# Sheet1.net
KiCad netlist of a schematic drawn in Altium Designer
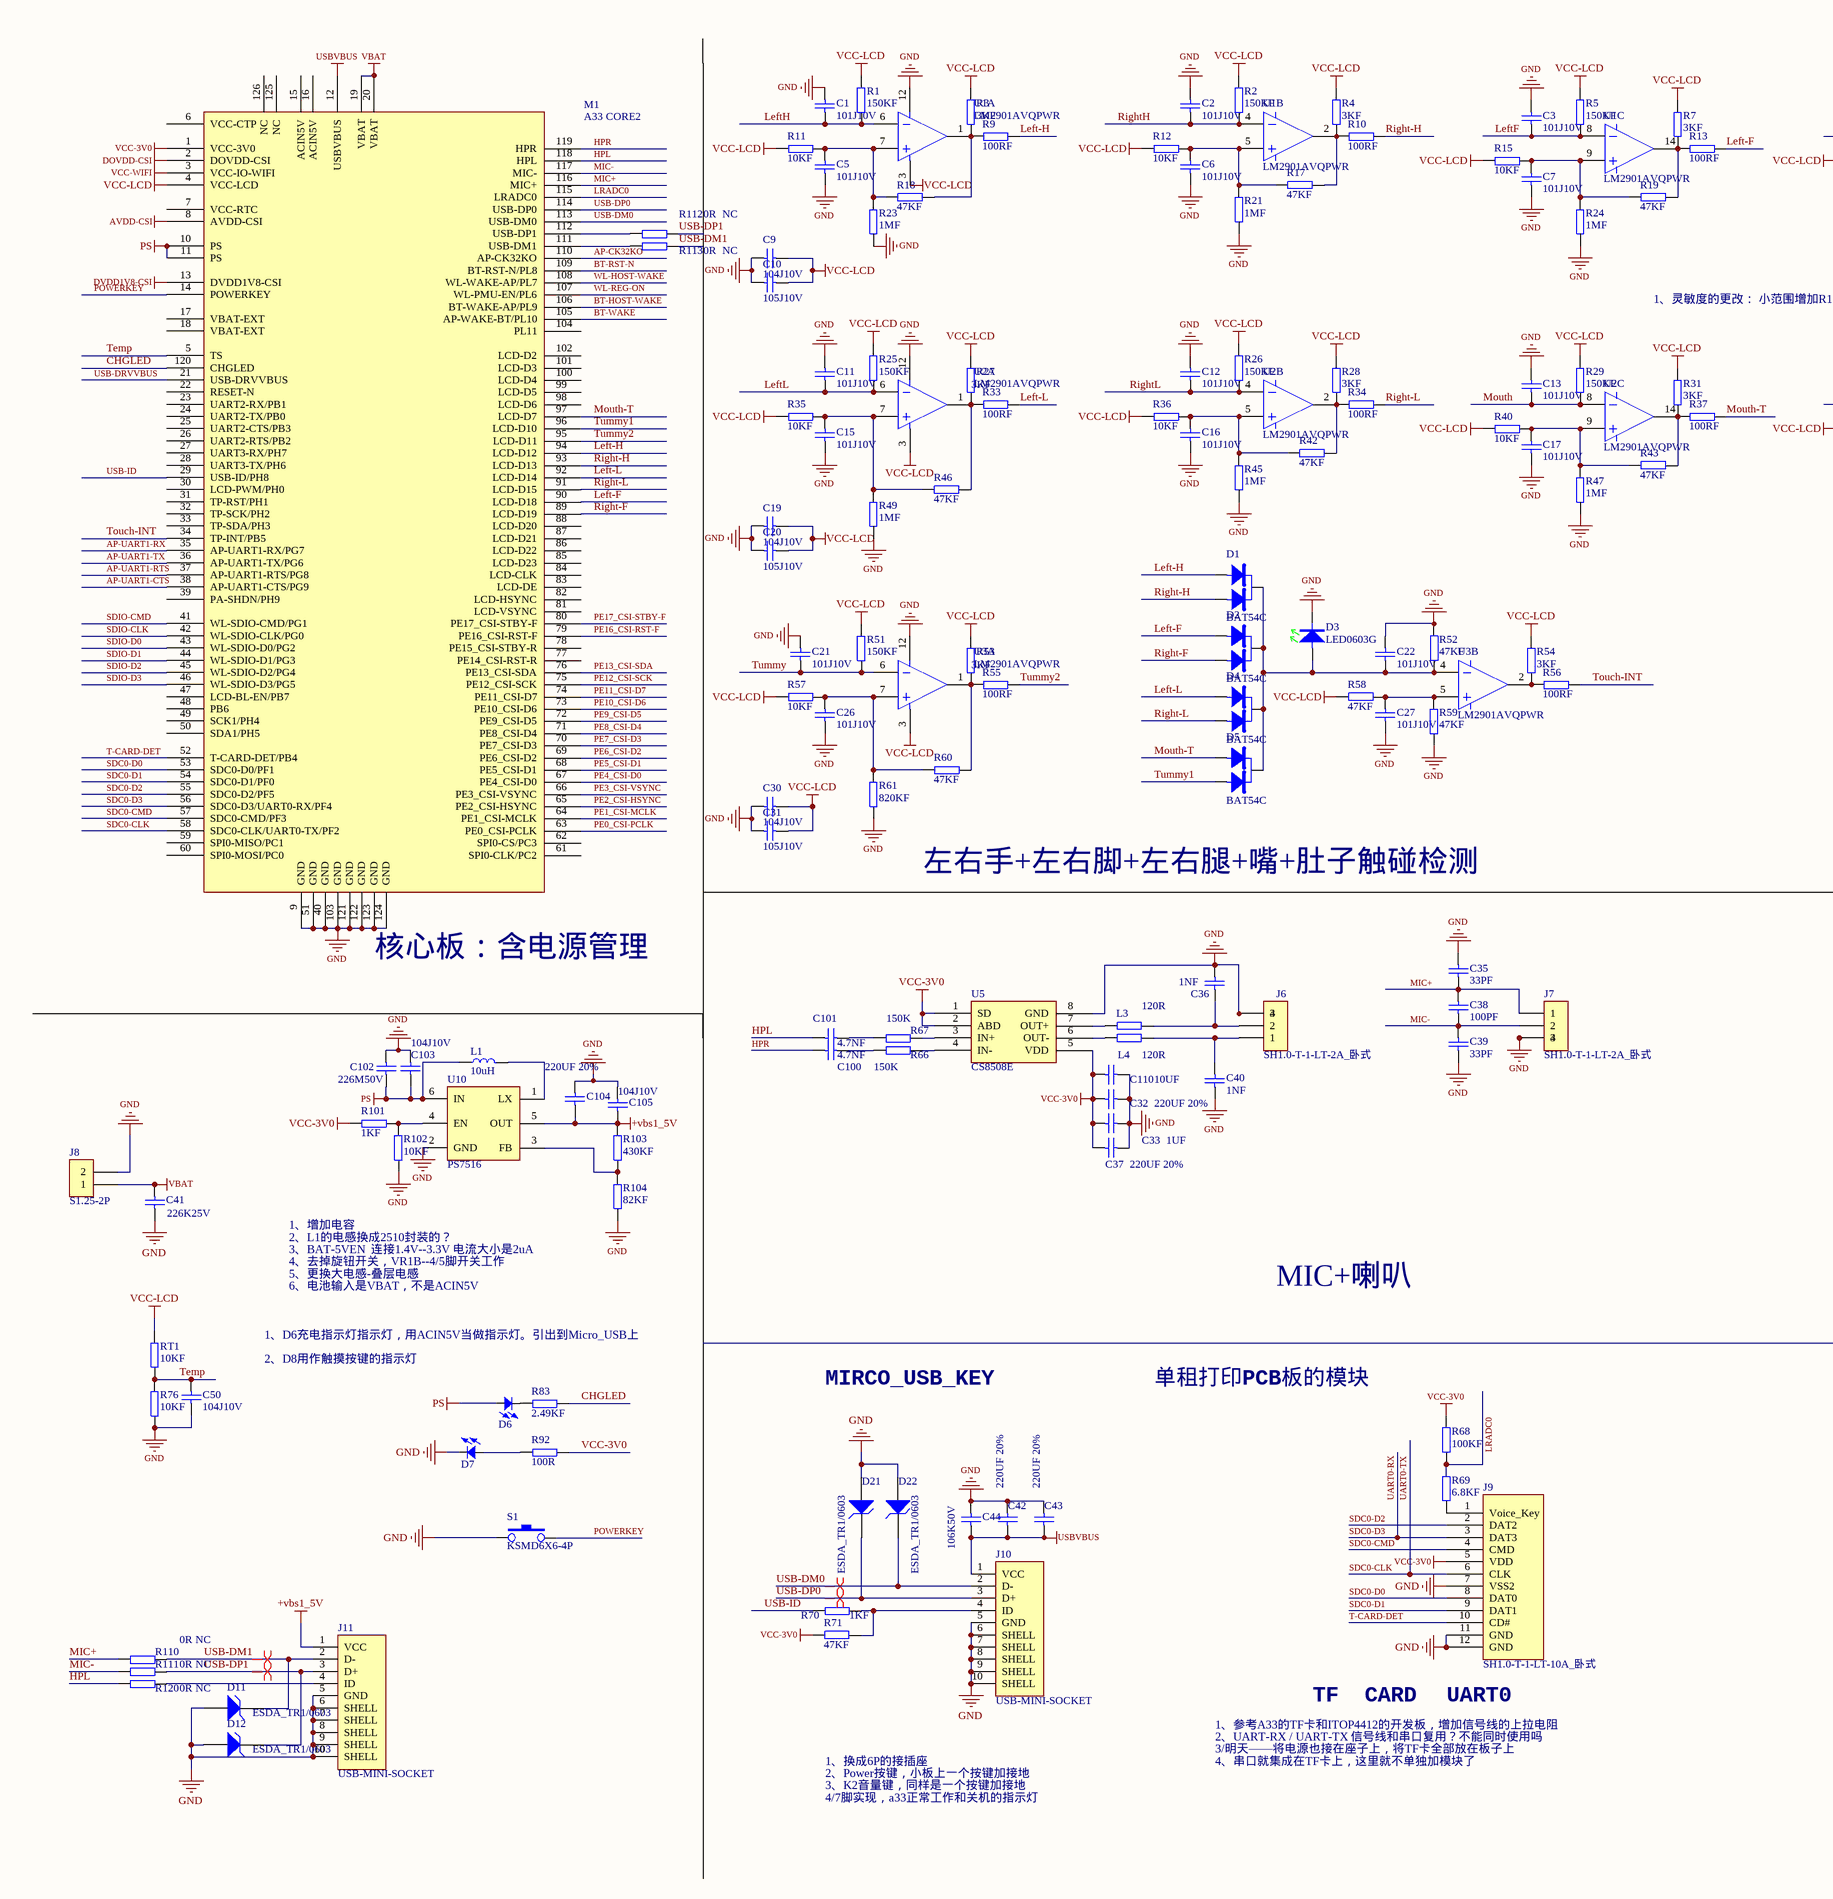
[diagram p0: Sheet1.SchDoc, left]
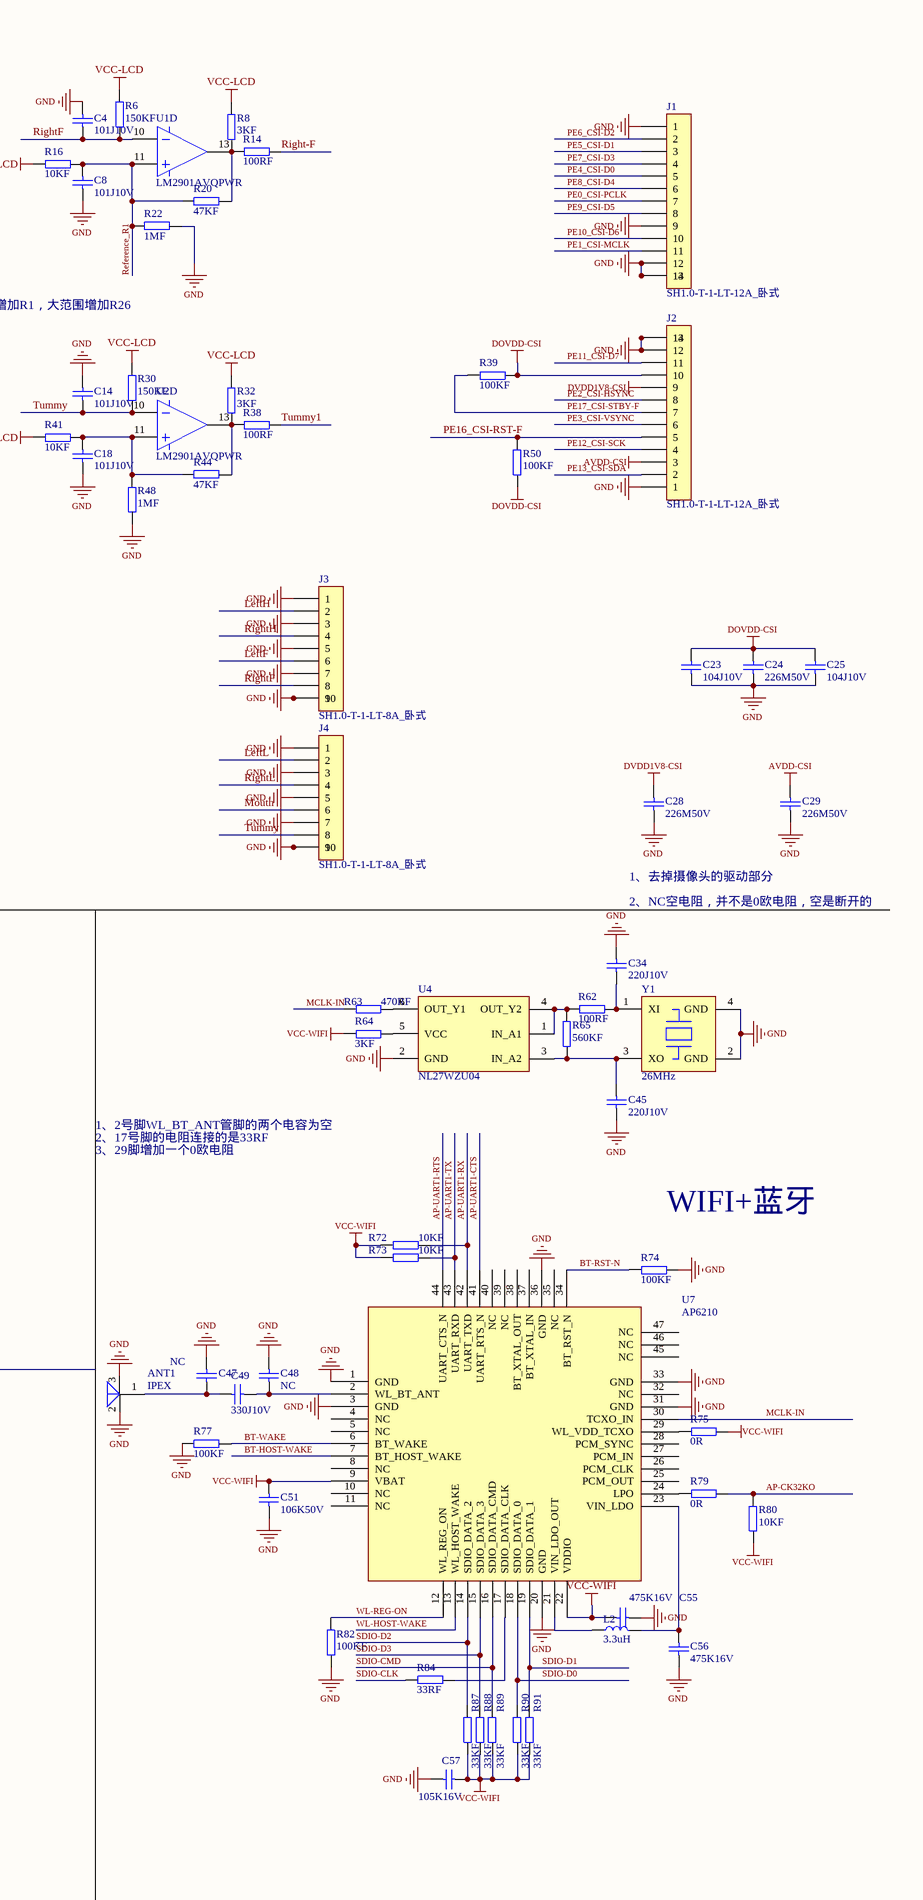
[diagram p1: Sheet1.SchDoc, right]

(export (version "E")
  (design (tool "Eeschema 10.0.6"))
  (components
    (comp (ref "ANT1")
      (value "IPEX")
      (footprint "J-IPEX")
      (description "天线接口IPEX")
      (libsource (lib "Connector") (part "J-IPEX"))
    )
    (comp (ref "C1")
      (value "101J10V")
      (footprint "C0402")
      (description "贴片电容-陶瓷")
      (libsource (lib "Capacitor") (part "C0402X7R-101J10V"))
    )
    (comp (ref "C2")
      (value "101J10V")
      (footprint "C0402")
      (description "贴片电容-陶瓷")
      (libsource (lib "Capacitor") (part "C0402X7R-101J10V"))
    )
    (comp (ref "C3")
      (value "101J10V")
      (footprint "C0402")
      (description "贴片电容-陶瓷")
      (libsource (lib "Capacitor") (part "C0402X7R-101J10V"))
    )
    (comp (ref "C4")
      (value "101J10V")
      (footprint "C0402")
      (description "贴片电容-陶瓷")
      (libsource (lib "Capacitor") (part "C0402X7R-101J10V"))
    )
    (comp (ref "C5")
      (value "101J10V")
      (footprint "C0402")
      (description "贴片电容-陶瓷")
      (libsource (lib "Capacitor") (part "C0402X7R-101J10V"))
    )
    (comp (ref "C6")
      (value "101J10V")
      (footprint "C0402")
      (description "贴片电容-陶瓷")
      (libsource (lib "Capacitor") (part "C0402X7R-101J10V"))
    )
    (comp (ref "C7")
      (value "101J10V")
      (footprint "C0402")
      (description "贴片电容-陶瓷")
      (libsource (lib "Capacitor") (part "C0402X7R-101J10V"))
    )
    (comp (ref "C8")
      (value "101J10V")
      (footprint "C0402")
      (description "贴片电容-陶瓷")
      (libsource (lib "Capacitor") (part "C0402X7R-101J10V"))
    )
    (comp (ref "C9")
      (value "104J10V")
      (footprint "C0402")
      (description "贴片电容-陶瓷")
      (libsource (lib "Capacitor") (part "C0402X7R-104J10V"))
    )
    (comp (ref "C10")
      (value "105J10V")
      (footprint "C0402")
      (description "贴片电容-陶瓷")
      (libsource (lib "Capacitor") (part "C0402X7R-105J10V"))
    )
    (comp (ref "C11")
      (value "101J10V")
      (footprint "C0402")
      (description "贴片电容-陶瓷")
      (libsource (lib "Capacitor") (part "C0402X7R-101J10V"))
    )
    (comp (ref "C12")
      (value "101J10V")
      (footprint "C0402")
      (description "贴片电容-陶瓷")
      (libsource (lib "Capacitor") (part "C0402X7R-101J10V"))
    )
    (comp (ref "C13")
      (value "101J10V")
      (footprint "C0402")
      (description "贴片电容-陶瓷")
      (libsource (lib "Capacitor") (part "C0402X7R-101J10V"))
    )
    (comp (ref "C14")
      (value "101J10V")
      (footprint "C0402")
      (description "贴片电容-陶瓷")
      (libsource (lib "Capacitor") (part "C0402X7R-101J10V"))
    )
    (comp (ref "C15")
      (value "101J10V")
      (footprint "C0402")
      (description "贴片电容-陶瓷")
      (libsource (lib "Capacitor") (part "C0402X7R-101J10V"))
    )
    (comp (ref "C16")
      (value "101J10V")
      (footprint "C0402")
      (description "贴片电容-陶瓷")
      (libsource (lib "Capacitor") (part "C0402X7R-101J10V"))
    )
    (comp (ref "C17")
      (value "101J10V")
      (footprint "C0402")
      (description "贴片电容-陶瓷")
      (libsource (lib "Capacitor") (part "C0402X7R-101J10V"))
    )
    (comp (ref "C18")
      (value "101J10V")
      (footprint "C0402")
      (description "贴片电容-陶瓷")
      (libsource (lib "Capacitor") (part "C0402X7R-101J10V"))
    )
    (comp (ref "C19")
      (value "104J10V")
      (footprint "C0402")
      (description "贴片电容-陶瓷")
      (libsource (lib "Capacitor") (part "C0402X7R-104J10V"))
    )
    (comp (ref "C20")
      (value "105J10V")
      (footprint "C0402")
      (description "贴片电容-陶瓷")
      (libsource (lib "Capacitor") (part "C0402X7R-105J10V"))
    )
    (comp (ref "C21")
      (value "101J10V")
      (footprint "C0402")
      (description "贴片电容-陶瓷")
      (libsource (lib "Capacitor") (part "C0402X7R-101J10V"))
    )
    (comp (ref "C22")
      (value "101J10V")
      (footprint "C0402")
      (description "贴片电容-陶瓷")
      (libsource (lib "Capacitor") (part "C0402X7R-101J10V"))
    )
    (comp (ref "C23")
      (value "104J10V")
      (footprint "C0402")
      (description "贴片电容-陶瓷")
      (libsource (lib "Capacitor") (part "C0402X7R-104J10V"))
    )
    (comp (ref "C24")
      (value "226M50V")
      (footprint "C0805")
      (description "贴片电容-陶瓷")
      (libsource (lib "Capacitor") (part "C0805Y5V-226M50V"))
    )
    (comp (ref "C25")
      (value "104J10V")
      (footprint "C0402")
      (description "贴片电容-陶瓷")
      (libsource (lib "Capacitor") (part "C0402X7R-104J10V"))
    )
    (comp (ref "C26")
      (value "101J10V")
      (footprint "C0402")
      (description "贴片电容-陶瓷")
      (libsource (lib "Capacitor") (part "C0402X7R-101J10V"))
    )
    (comp (ref "C27")
      (value "101J10V")
      (footprint "C0402")
      (description "贴片电容-陶瓷")
      (libsource (lib "Capacitor") (part "C0402X7R-101J10V"))
    )
    (comp (ref "C28")
      (value "226M50V")
      (footprint "C0805")
      (description "贴片电容-陶瓷")
      (libsource (lib "Capacitor") (part "C0805Y5V-226M50V"))
    )
    (comp (ref "C29")
      (value "226M50V")
      (footprint "C0805")
      (description "贴片电容-陶瓷")
      (libsource (lib "Capacitor") (part "C0805Y5V-226M50V"))
    )
    (comp (ref "C30")
      (value "104J10V")
      (footprint "C0402")
      (description "贴片电容-陶瓷")
      (libsource (lib "Capacitor") (part "C0402X7R-104J10V"))
    )
    (comp (ref "C31")
      (value "105J10V")
      (footprint "C0402")
      (description "贴片电容-陶瓷")
      (libsource (lib "Capacitor") (part "C0402X7R-105J10V"))
    )
    (comp (ref "C32")
      (value "220UF 20%")
      (footprint "C1206")
      (description "C 1206钽电容 --220UF 10V 3216 A型 有极性电容 3.2mm X 1.6mm")
      (libsource (lib "Capacitor") (part "C1206-A型 极性电容"))
    )
    (comp (ref "C33")
      (value "1UF")
      (footprint "C0402")
      (description "贴片电容-陶瓷")
      (libsource (lib "Capacitor") (part "C0402X7R-105J10V"))
    )
    (comp (ref "C34")
      (value "220J10V")
      (footprint "C0402")
      (description "贴片电容-陶瓷")
      (libsource (lib "Capacitor") (part "C0402X7R-220J10V"))
    )
    (comp (ref "C35")
      (value "33PF")
      (footprint "C0402")
      (description "贴片电容-陶瓷")
      (libsource (lib "Capacitor") (part "C0402X7R-104J10V"))
    )
    (comp (ref "C36")
      (value "1NF")
      (footprint "C0402")
      (description "贴片电容-陶瓷")
      (libsource (lib "Capacitor") (part "C0402X7R-220J10V"))
    )
    (comp (ref "C37")
      (value "220UF 20%")
      (footprint "C1206")
      (description "C 1206钽电容 --220UF 10V 3216 A型 有极性电容 3.2mm X 1.6mm")
      (libsource (lib "Capacitor") (part "C1206-A型 极性电容"))
    )
    (comp (ref "C38")
      (value "100PF")
      (footprint "C0402")
      (description "贴片电容-陶瓷")
      (libsource (lib "Capacitor") (part "C0402X7R-104J10V"))
    )
    (comp (ref "C39")
      (value "33PF")
      (footprint "C0402")
      (description "贴片电容-陶瓷")
      (libsource (lib "Capacitor") (part "C0402X7R-104J10V"))
    )
    (comp (ref "C40")
      (value "1NF")
      (footprint "C0402")
      (description "贴片电容-陶瓷")
      (libsource (lib "Capacitor") (part "C0402X7R-220J10V"))
    )
    (comp (ref "C41")
      (value "226K25V")
      (footprint "C0805")
      (description "贴片电容-陶瓷")
      (libsource (lib "Capacitor") (part "C0805X7R-226K25V"))
    )
    (comp (ref "C42")
      (value "220UF 20%")
      (footprint "C1206")
      (description "C 1206钽电容 --220UF 10V 3216 A型 有极性电容 3.2mm X 1.6mm")
      (libsource (lib "Capacitor") (part "C1206-A型 极性电容"))
    )
    (comp (ref "C43")
      (value "220UF 20%")
      (footprint "C1206")
      (description "C 1206钽电容 --220UF 10V 3216 A型 有极性电容 3.2mm X 1.6mm")
      (libsource (lib "Capacitor") (part "C1206-A型 极性电容"))
    )
    (comp (ref "C44")
      (value "106K50V")
      (footprint "C0603")
      (description "贴片电容-陶瓷")
      (libsource (lib "Capacitor") (part "C0603X7R-106K50V"))
    )
    (comp (ref "C45")
      (value "220J10V")
      (footprint "C0402")
      (description "贴片电容-陶瓷")
      (libsource (lib "Capacitor") (part "C0402X7R-220J10V"))
    )
    (comp (ref "C47")
      (value "NC")
      (footprint "C0402")
      (description "贴片电容-陶瓷")
      (libsource (lib "Capacitor") (part "C0402X7R-220J10V"))
    )
    (comp (ref "C48")
      (value "NC")
      (footprint "C0402")
      (description "贴片电容-陶瓷")
      (libsource (lib "Capacitor") (part "C0402X7R-220J10V"))
    )
    (comp (ref "C49")
      (value "330J10V")
      (footprint "C0402")
      (description "贴片电容-陶瓷")
      (libsource (lib "Capacitor") (part "C0402X7R-330J10V"))
    )
    (comp (ref "C50")
      (value "104J10V")
      (footprint "C0402")
      (description "贴片电容-陶瓷")
      (libsource (lib "Capacitor") (part "C0402X7R-104J10V"))
    )
    (comp (ref "C51")
      (value "106K50V")
      (footprint "C0603")
      (description "贴片电容-陶瓷")
      (libsource (lib "Capacitor") (part "C0603X7R-106K50V"))
    )
    (comp (ref "C55")
      (value "475K16V")
      (footprint "C0603")
      (description "贴片电容-陶瓷")
      (libsource (lib "Capacitor") (part "C0603X7R-475K16V"))
    )
    (comp (ref "C56")
      (value "475K16V")
      (footprint "C0603")
      (description "贴片电容-陶瓷")
      (libsource (lib "Capacitor") (part "C0603X7R-475K16V"))
    )
    (comp (ref "C57")
      (value "105K16V")
      (footprint "C0603")
      (description "贴片电容-陶瓷")
      (libsource (lib "Capacitor") (part "C0603X7R-105K16V"))
    )
    (comp (ref "C100")
      (value "4.7NF")
      (footprint "C0603")
      (description "贴片电容-陶瓷")
      (libsource (lib "Capacitor") (part "C0603X7R-330J25V"))
    )
    (comp (ref "C101")
      (value "4.7NF")
      (footprint "C0603")
      (description "贴片电容-陶瓷")
      (libsource (lib "Capacitor") (part "C0603X7R-330J25V"))
    )
    (comp (ref "C102")
      (value "226M50V")
      (footprint "C0805")
      (description "贴片电容-陶瓷")
      (libsource (lib "Capacitor") (part "C0805Y5V-226M50V"))
    )
    (comp (ref "C103")
      (value "104J10V")
      (footprint "C0402")
      (description "贴片电容-陶瓷")
      (libsource (lib "Capacitor") (part "C0402X7R-104J10V"))
    )
    (comp (ref "C104")
      (value "220UF 20%")
      (footprint "C1206")
      (description "C 1206钽电容 --220UF 10V 3216 A型 有极性电容 3.2mm X 1.6mm")
      (libsource (lib "Capacitor") (part "C1206-A型 极性电容"))
    )
    (comp (ref "C105")
      (value "104J10V")
      (footprint "C0402")
      (description "贴片电容-陶瓷")
      (libsource (lib "Capacitor") (part "C0402X7R-104J10V"))
    )
    (comp (ref "C110")
      (value "10UF")
      (footprint "C0603")
      (description "贴片电容-陶瓷")
      (libsource (lib "Capacitor") (part "C0603X7R-330J25V"))
    )
    (comp (ref "D1")
      (value "BAT54C")
      (footprint "U-SOT-23-3")
      (description "贴片二极管-肖特基")
      (libsource (lib "Diode") (part "BAT54C"))
    )
    (comp (ref "D2")
      (value "BAT54C")
      (footprint "U-SOT-23-3")
      (description "贴片二极管-肖特基")
      (libsource (lib "Diode") (part "BAT54C"))
    )
    (comp (ref "D3")
      (value "LED0603G")
      (footprint "D-LED0603G")
      (description "贴片二极管-LED")
      (libsource (lib "Diode") (part "DLED-0603-G"))
    )
    (comp (ref "D4")
      (value "BAT54C")
      (footprint "U-SOT-23-3")
      (description "贴片二极管-肖特基")
      (libsource (lib "Diode") (part "BAT54C"))
    )
    (comp (ref "D5")
      (value "BAT54C")
      (footprint "U-SOT-23-3")
      (description "贴片二极管-肖特基")
      (libsource (lib "Diode") (part "BAT54C"))
    )
    (comp (ref "D6") (value "发光二极管") (footprint "PCB11:LEDΦ5-H12") (libsource (lib "1_1") (part "发光二极管")))
    (comp (ref "D7") (value "发光二极管") (footprint "PCB11:LEDΦ5-H12") (libsource (lib "1_1") (part "发光二极管")))
    (comp (ref "D11")
      (value "ESDA_TR1/0603")
      (footprint "HS_0603D")
      (description "Zener Diode")
      (fields (field (name "PUBLISHER") "*"))
      (libsource (lib "HSC32K1(QFN56)_BlueTooth_V2.0_20171108 - 副本") (part "D Zener"))
    )
    (comp (ref "D12")
      (value "ESDA_TR1/0603")
      (footprint "HS_0603D")
      (description "Zener Diode")
      (fields (field (name "PUBLISHER") "*"))
      (libsource (lib "HSC32K1(QFN56)_BlueTooth_V2.0_20171108 - 副本") (part "D Zener"))
    )
    (comp (ref "D21")
      (value "ESDA_TR1/0603")
      (footprint "HS_0603D")
      (description "Zener Diode")
      (fields (field (name "PUBLISHER") "*"))
      (libsource (lib "1_1") (part "D Zener"))
    )
    (comp (ref "D22")
      (value "ESDA_TR1/0603")
      (footprint "HS_0603D")
      (description "Zener Diode")
      (fields (field (name "PUBLISHER") "*"))
      (libsource (lib "1_1") (part "D Zener"))
    )
    (comp (ref "J1")
      (value "SH1.0-T-1-LT-12A_卧式")
      (footprint "J-SH1.0-T-1-LT-12A_卧式")
      (libsource (lib "Connector") (part "SH1.0-T-1-LT-12A_卧式"))
    )
    (comp (ref "J2")
      (value "SH1.0-T-1-LT-12A_卧式")
      (footprint "J-SH1.0-T-1-LT-12A_卧式")
      (libsource (lib "") (part "SH1.0-T-1-LT-12A_卧式_1"))
    )
    (comp (ref "J3")
      (value "SH1.0-T-1-LT-8A_卧式")
      (footprint "J-SH1.0-T-1-LT-8A_卧式")
      (description "SH1.0-T-1-LT-6A_卧式")
      (libsource (lib "Connector") (part "SH1.0-T-1-LT-8A_卧式"))
    )
    (comp (ref "J4")
      (value "SH1.0-T-1-LT-8A_卧式")
      (footprint "J-SH1.0-T-1-LT-8A_卧式")
      (description "SH1.0-T-1-LT-6A_卧式")
      (libsource (lib "Connector") (part "SH1.0-T-1-LT-8A_卧式"))
    )
    (comp (ref "J6")
      (value "SH1.0-T-1-LT-2A_卧式")
      (footprint "J-SH1.0-T-1-LT-2A_卧式")
      (libsource (lib "") (part "SH1.0-T-1-LT-2A_卧式_1"))
    )
    (comp (ref "J7")
      (value "SH1.0-T-1-LT-2A_卧式")
      (footprint "J-SH1.0-T-1-LT-2A_卧式")
      (libsource (lib "Connector") (part "SH1.0-T-1-LT-2A_卧式"))
    )
    (comp (ref "J8")
      (value "S1.25-2P")
      (footprint "PCB11:S1.25-2P")
      (description "定制铜排")
      (libsource (lib "Others") (part "O-CP-840-2P"))
    )
    (comp (ref "J9")
      (value "SH1.0-T-1-LT-10A_卧式")
      (footprint "J-SH1.0-T-1-LT-10A_卧式")
      (libsource (lib "Connector") (part "SH1.0-T-1-LT-10A_卧式"))
    )
    (comp (ref "J10")
      (value "USB-MINI-SOCKET")
      (footprint "MICRO-USB - 5.9")
      (description "USB-A卧式插座")
      (libsource (lib "Connector") (part "J-USB-MINI-SOCKET"))
    )
    (comp (ref "J11")
      (value "USB-MINI-SOCKET")
      (footprint "MICRO-USB - 5.9")
      (description "USB-A卧式插座")
      (libsource (lib "Connector") (part "J-USB-MINI-SOCKET"))
    )
    (comp (ref "L1")
      (value "10uH")
      (footprint "L-2520")
      (description "贴片电感-层叠")
      (libsource (lib "magnetic") (part "L-2520-10uH"))
    )
    (comp (ref "L2")
      (value "3.3uH")
      (footprint "L0805")
      (description "贴片电感-层叠")
      (libsource (lib "magnetic") (part "L-0805-3.3uH"))
    )
    (comp (ref "L3")
      (value "120R")
      (footprint "R0603")
      (description "贴片电阻-通用")
      (libsource (lib "Resistor") (part "R0603-47KF"))
    )
    (comp (ref "L4")
      (value "120R")
      (footprint "R0603")
      (description "贴片电阻-通用")
      (libsource (lib "Resistor") (part "R0603-47KF"))
    )
    (comp (ref "M1")
      (value "A33 CORE2")
      (footprint "AIWAC-bolster-V02:A33-CORE2")
      (libsource (lib "Module") (part "A33 CORE2"))
    )
    (comp (ref "R1")
      (value "150KF")
      (footprint "R0603")
      (description "贴片电阻-通用")
      (libsource (lib "Resistor") (part "R0603-150KF"))
    )
    (comp (ref "R2")
      (value "150KF")
      (footprint "R0603")
      (description "贴片电阻-通用")
      (libsource (lib "Resistor") (part "R0603-150KF"))
    )
    (comp (ref "R3")
      (value "3KF")
      (footprint "R0603")
      (description "贴片电阻-通用")
      (libsource (lib "Resistor") (part "R0603-3KF"))
    )
    (comp (ref "R4")
      (value "3KF")
      (footprint "R0603")
      (description "贴片电阻-通用")
      (libsource (lib "Resistor") (part "R0603-3KF"))
    )
    (comp (ref "R5")
      (value "150KF")
      (footprint "R0603")
      (description "贴片电阻-通用")
      (libsource (lib "Resistor") (part "R0603-150KF"))
    )
    (comp (ref "R6")
      (value "150KF")
      (footprint "R0603")
      (description "贴片电阻-通用")
      (libsource (lib "Resistor") (part "R0603-150KF"))
    )
    (comp (ref "R7")
      (value "3KF")
      (footprint "R0603")
      (description "贴片电阻-通用")
      (libsource (lib "Resistor") (part "R0603-3KF"))
    )
    (comp (ref "R8")
      (value "3KF")
      (footprint "R0603")
      (description "贴片电阻-通用")
      (libsource (lib "Resistor") (part "R0603-3KF"))
    )
    (comp (ref "R9")
      (value "100RF")
      (footprint "R0603")
      (description "贴片电阻-通用")
      (libsource (lib "Resistor") (part "R0603-100RF"))
    )
    (comp (ref "R10")
      (value "100RF")
      (footprint "R0603")
      (description "贴片电阻-通用")
      (libsource (lib "Resistor") (part "R0603-100RF"))
    )
    (comp (ref "R11")
      (value "10KF")
      (footprint "R0603")
      (description "贴片电阻-通用")
      (libsource (lib "Resistor") (part "R0603-10KF"))
    )
    (comp (ref "R12")
      (value "10KF")
      (footprint "R0603")
      (description "贴片电阻-通用")
      (libsource (lib "Resistor") (part "R0603-10KF"))
    )
    (comp (ref "R13")
      (value "100RF")
      (footprint "R0603")
      (description "贴片电阻-通用")
      (libsource (lib "Resistor") (part "R0603-100RF"))
    )
    (comp (ref "R14")
      (value "100RF")
      (footprint "R0603")
      (description "贴片电阻-通用")
      (libsource (lib "Resistor") (part "R0603-100RF"))
    )
    (comp (ref "R15")
      (value "10KF")
      (footprint "R0603")
      (description "贴片电阻-通用")
      (libsource (lib "Resistor") (part "R0603-10KF"))
    )
    (comp (ref "R16")
      (value "10KF")
      (footprint "R0603")
      (description "贴片电阻-通用")
      (libsource (lib "Resistor") (part "R0603-10KF"))
    )
    (comp (ref "R17")
      (value "47KF")
      (footprint "R0603")
      (description "贴片电阻-通用")
      (libsource (lib "Resistor") (part "R0603-47KF"))
    )
    (comp (ref "R18")
      (value "47KF")
      (footprint "R0603")
      (description "贴片电阻-通用")
      (libsource (lib "Resistor") (part "R0603-47KF"))
    )
    (comp (ref "R19")
      (value "47KF")
      (footprint "R0603")
      (description "贴片电阻-通用")
      (libsource (lib "Resistor") (part "R0603-47KF"))
    )
    (comp (ref "R20")
      (value "47KF")
      (footprint "R0603")
      (description "贴片电阻-通用")
      (libsource (lib "Resistor") (part "R0603-47KF"))
    )
    (comp (ref "R21")
      (value "1MF")
      (footprint "R0603")
      (description "贴片电阻-通用")
      (libsource (lib "Resistor") (part "R0603-1MF"))
    )
    (comp (ref "R22")
      (value "1MF")
      (footprint "R0603")
      (description "贴片电阻-通用")
      (libsource (lib "Resistor") (part "R0603-1MF"))
    )
    (comp (ref "R23")
      (value "1MF")
      (footprint "R0603")
      (description "贴片电阻-通用")
      (libsource (lib "Resistor") (part "R0603-1MF"))
    )
    (comp (ref "R24")
      (value "1MF")
      (footprint "R0603")
      (description "贴片电阻-通用")
      (libsource (lib "Resistor") (part "R0603-1MF"))
    )
    (comp (ref "R25")
      (value "150KF")
      (footprint "R0603")
      (description "贴片电阻-通用")
      (libsource (lib "Resistor") (part "R0603-150KF"))
    )
    (comp (ref "R26")
      (value "150KF")
      (footprint "R0603")
      (description "贴片电阻-通用")
      (libsource (lib "Resistor") (part "R0603-150KF"))
    )
    (comp (ref "R27")
      (value "3KF")
      (footprint "R0603")
      (description "贴片电阻-通用")
      (libsource (lib "Resistor") (part "R0603-3KF"))
    )
    (comp (ref "R28")
      (value "3KF")
      (footprint "R0603")
      (description "贴片电阻-通用")
      (libsource (lib "Resistor") (part "R0603-3KF"))
    )
    (comp (ref "R29")
      (value "150KF")
      (footprint "R0603")
      (description "贴片电阻-通用")
      (libsource (lib "Resistor") (part "R0603-150KF"))
    )
    (comp (ref "R30")
      (value "150KF")
      (footprint "R0603")
      (description "贴片电阻-通用")
      (libsource (lib "Resistor") (part "R0603-150KF"))
    )
    (comp (ref "R31")
      (value "3KF")
      (footprint "R0603")
      (description "贴片电阻-通用")
      (libsource (lib "Resistor") (part "R0603-3KF"))
    )
    (comp (ref "R32")
      (value "3KF")
      (footprint "R0603")
      (description "贴片电阻-通用")
      (libsource (lib "Resistor") (part "R0603-3KF"))
    )
    (comp (ref "R33")
      (value "100RF")
      (footprint "R0603")
      (description "贴片电阻-通用")
      (libsource (lib "Resistor") (part "R0603-100RF"))
    )
    (comp (ref "R34")
      (value "100RF")
      (footprint "R0603")
      (description "贴片电阻-通用")
      (libsource (lib "Resistor") (part "R0603-100RF"))
    )
    (comp (ref "R35")
      (value "10KF")
      (footprint "R0603")
      (description "贴片电阻-通用")
      (libsource (lib "Resistor") (part "R0603-10KF"))
    )
    (comp (ref "R36")
      (value "10KF")
      (footprint "R0603")
      (description "贴片电阻-通用")
      (libsource (lib "Resistor") (part "R0603-10KF"))
    )
    (comp (ref "R37")
      (value "100RF")
      (footprint "R0603")
      (description "贴片电阻-通用")
      (libsource (lib "Resistor") (part "R0603-100RF"))
    )
    (comp (ref "R38")
      (value "100RF")
      (footprint "R0603")
      (description "贴片电阻-通用")
      (libsource (lib "Resistor") (part "R0603-100RF"))
    )
    (comp (ref "R39")
      (value "100KF")
      (footprint "R0603")
      (description "贴片电阻-通用")
      (libsource (lib "Resistor") (part "R0603-100KF"))
    )
    (comp (ref "R40")
      (value "10KF")
      (footprint "R0603")
      (description "贴片电阻-通用")
      (libsource (lib "Resistor") (part "R0603-10KF"))
    )
    (comp (ref "R41")
      (value "10KF")
      (footprint "R0603")
      (description "贴片电阻-通用")
      (libsource (lib "Resistor") (part "R0603-10KF"))
    )
    (comp (ref "R42")
      (value "47KF")
      (footprint "R0603")
      (description "贴片电阻-通用")
      (libsource (lib "Resistor") (part "R0603-47KF"))
    )
    (comp (ref "R43")
      (value "47KF")
      (footprint "R0603")
      (description "贴片电阻-通用")
      (libsource (lib "Resistor") (part "R0603-47KF"))
    )
    (comp (ref "R44")
      (value "47KF")
      (footprint "R0603")
      (description "贴片电阻-通用")
      (libsource (lib "Resistor") (part "R0603-47KF"))
    )
    (comp (ref "R45")
      (value "1MF")
      (footprint "R0603")
      (description "贴片电阻-通用")
      (libsource (lib "Resistor") (part "R0603-1MF"))
    )
    (comp (ref "R46")
      (value "47KF")
      (footprint "R0603")
      (description "贴片电阻-通用")
      (libsource (lib "Resistor") (part "R0603-47KF"))
    )
    (comp (ref "R47")
      (value "1MF")
      (footprint "R0603")
      (description "贴片电阻-通用")
      (libsource (lib "Resistor") (part "R0603-1MF"))
    )
    (comp (ref "R48")
      (value "1MF")
      (footprint "R0603")
      (description "贴片电阻-通用")
      (libsource (lib "Resistor") (part "R0603-1MF"))
    )
    (comp (ref "R49")
      (value "1MF")
      (footprint "R0603")
      (description "贴片电阻-通用")
      (libsource (lib "Resistor") (part "R0603-1MF"))
    )
    (comp (ref "R50")
      (value "100KF")
      (footprint "R0603")
      (description "贴片电阻-通用")
      (libsource (lib "Resistor") (part "R0603-100KF"))
    )
    (comp (ref "R51")
      (value "150KF")
      (footprint "R0603")
      (description "贴片电阻-通用")
      (libsource (lib "Resistor") (part "R0603-150KF"))
    )
    (comp (ref "R52")
      (value "47KF")
      (footprint "R0603")
      (description "贴片电阻-通用")
      (libsource (lib "Resistor") (part "R0603-47KF"))
    )
    (comp (ref "R53")
      (value "3KF")
      (footprint "R0603")
      (description "贴片电阻-通用")
      (libsource (lib "Resistor") (part "R0603-3KF"))
    )
    (comp (ref "R54")
      (value "3KF")
      (footprint "R0603")
      (description "贴片电阻-通用")
      (libsource (lib "Resistor") (part "R0603-3KF"))
    )
    (comp (ref "R55")
      (value "100RF")
      (footprint "R0603")
      (description "贴片电阻-通用")
      (libsource (lib "Resistor") (part "R0603-100RF"))
    )
    (comp (ref "R56")
      (value "100RF")
      (footprint "R0603")
      (description "贴片电阻-通用")
      (libsource (lib "Resistor") (part "R0603-100RF"))
    )
    (comp (ref "R57")
      (value "10KF")
      (footprint "R0603")
      (description "贴片电阻-通用")
      (libsource (lib "Resistor") (part "R0603-10KF"))
    )
    (comp (ref "R58")
      (value "47KF")
      (footprint "R0603")
      (description "贴片电阻-通用")
      (libsource (lib "Resistor") (part "R0603-47KF"))
    )
    (comp (ref "R59")
      (value "47KF")
      (footprint "R0603")
      (description "贴片电阻-通用")
      (libsource (lib "Resistor") (part "R0603-10KF"))
    )
    (comp (ref "R60")
      (value "47KF")
      (footprint "R0603")
      (description "贴片电阻-通用")
      (libsource (lib "Resistor") (part "R0603-10KF"))
    )
    (comp (ref "R61")
      (value "820KF")
      (footprint "R0603")
      (description "贴片电阻-通用")
      (libsource (lib "Resistor") (part "R0603-820KF"))
    )
    (comp (ref "R62")
      (value "100RF")
      (footprint "R0603")
      (description "贴片电阻-通用")
      (libsource (lib "Resistor") (part "R0603-100RF"))
    )
    (comp (ref "R63")
      (value "470RF")
      (footprint "R0603")
      (description "贴片电阻-通用")
      (libsource (lib "Resistor") (part "R0603-470RF"))
    )
    (comp (ref "R64")
      (value "3KF")
      (footprint "R0603")
      (description "贴片电阻-通用")
      (libsource (lib "Resistor") (part "R0603-3KF"))
    )
    (comp (ref "R65")
      (value "560KF")
      (footprint "R0603")
      (description "贴片电阻-通用")
      (libsource (lib "Resistor") (part "R0603-560KF"))
    )
    (comp (ref "R66")
      (value "150K")
      (footprint "R0603")
      (description "贴片电阻-通用")
      (libsource (lib "Resistor") (part "R0603-10KF"))
    )
    (comp (ref "R67")
      (value "150K")
      (footprint "R0603")
      (description "贴片电阻-通用")
      (libsource (lib "Resistor") (part "R0603-10KF"))
    )
    (comp (ref "R68")
      (value "100KF")
      (footprint "R0603")
      (description "贴片电阻-通用")
      (libsource (lib "Resistor") (part "R0603-100KF"))
    )
    (comp (ref "R69")
      (value "6.8KF")
      (footprint "R0603")
      (description "贴片电阻-通用")
      (libsource (lib "Resistor") (part "R0603-6.8KF"))
    )
    (comp (ref "R70")
      (value "1KF")
      (footprint "R0603")
      (description "贴片电阻-通用")
      (libsource (lib "Resistor") (part "R0603-1KF"))
    )
    (comp (ref "R71")
      (value "47KF")
      (footprint "R0603")
      (description "贴片电阻-通用")
      (libsource (lib "Resistor") (part "R0603-47KF"))
    )
    (comp (ref "R72")
      (value "10KF")
      (footprint "R0603")
      (description "贴片电阻-通用")
      (libsource (lib "Resistor") (part "R0603-10KF"))
    )
    (comp (ref "R73")
      (value "10KF")
      (footprint "R0603")
      (description "贴片电阻-通用")
      (libsource (lib "Resistor") (part "R0603-10KF"))
    )
    (comp (ref "R74")
      (value "100KF")
      (footprint "R0603")
      (description "贴片电阻-通用")
      (libsource (lib "Resistor") (part "R0603-100KF"))
    )
    (comp (ref "R75")
      (value "0R")
      (footprint "R0603")
      (description "贴片电阻-通用")
      (libsource (lib "Resistor") (part "R0603-0R"))
    )
    (comp (ref "R76")
      (value "10KF")
      (footprint "R0603")
      (description "贴片电阻-通用")
      (libsource (lib "Resistor") (part "R0603-10KF"))
    )
    (comp (ref "R77")
      (value "100KF")
      (footprint "R0603")
      (description "贴片电阻-通用")
      (libsource (lib "Resistor") (part "R0603-100KF"))
    )
    (comp (ref "R79")
      (value "0R")
      (footprint "R0603")
      (description "贴片电阻-通用")
      (libsource (lib "Resistor") (part "R0603-0R"))
    )
    (comp (ref "R80")
      (value "10KF")
      (footprint "R0603")
      (description "贴片电阻-通用")
      (libsource (lib "Resistor") (part "R0603-10KF"))
    )
    (comp (ref "R82")
      (value "100KF")
      (footprint "R0603")
      (description "贴片电阻-通用")
      (libsource (lib "Resistor") (part "R0603-100KF"))
    )
    (comp (ref "R83")
      (value "2.49KF")
      (footprint "R0603")
      (description "贴片电阻-通用")
      (libsource (lib "Resistor") (part "R0603-3KF"))
    )
    (comp (ref "R84")
      (value "33RF")
      (footprint "R0603")
      (description "贴片电阻-通用")
      (libsource (lib "Resistor") (part "R0603-33RF"))
    )
    (comp (ref "R87")
      (value "33KF")
      (footprint "R0603")
      (description "贴片电阻-通用")
      (libsource (lib "Resistor") (part "R0603-33KF"))
    )
    (comp (ref "R88")
      (value "33KF")
      (footprint "R0603")
      (description "贴片电阻-通用")
      (libsource (lib "Resistor") (part "R0603-33KF"))
    )
    (comp (ref "R89")
      (value "33KF")
      (footprint "R0603")
      (description "贴片电阻-通用")
      (libsource (lib "Resistor") (part "R0603-33KF"))
    )
    (comp (ref "R90")
      (value "33KF")
      (footprint "R0603")
      (description "贴片电阻-通用")
      (libsource (lib "Resistor") (part "R0603-33KF"))
    )
    (comp (ref "R91")
      (value "33KF")
      (footprint "R0603")
      (description "贴片电阻-通用")
      (libsource (lib "Resistor") (part "R0603-33KF"))
    )
    (comp (ref "R92")
      (value "100R")
      (footprint "R0603")
      (description "贴片电阻-通用")
      (libsource (lib "Resistor") (part "R0603-2KF"))
    )
    (comp (ref "R101")
      (value "1KF")
      (footprint "R0603")
      (description "贴片电阻-通用")
      (libsource (lib "Resistor") (part "R0603-1KF"))
    )
    (comp (ref "R102")
      (value "10KF")
      (footprint "R0603")
      (description "贴片电阻-通用")
      (libsource (lib "Resistor") (part "R0603-10KF"))
    )
    (comp (ref "R103")
      (value "430KF")
      (footprint "R0603")
      (description "贴片电阻-通用")
      (libsource (lib "Resistor") (part "R0603-430KF"))
    )
    (comp (ref "R104")
      (value "82KF")
      (footprint "R0603")
      (description "贴片电阻-通用")
      (libsource (lib "Resistor") (part "R0603-82KF"))
    )
    (comp (ref "R110")
      (value "0R NC")
      (footprint "R0603")
      (description "贴片电阻-通用")
      (libsource (lib "Resistor") (part "R0603-2KF"))
    )
    (comp (ref "R111")
      (value "0R NC")
      (footprint "R0603")
      (description "贴片电阻-通用")
      (libsource (lib "Resistor") (part "R0603-2KF"))
    )
    (comp (ref "R112")
      (value "0R  NC")
      (footprint "R0603")
      (description "贴片电阻-通用")
      (libsource (lib "Resistor") (part "R0603-10KF"))
    )
    (comp (ref "R113")
      (value "0R  NC")
      (footprint "R0603")
      (description "贴片电阻-通用")
      (libsource (lib "Resistor") (part "R0603-10KF"))
    )
    (comp (ref "R120")
      (value "0R NC")
      (footprint "R0603")
      (description "贴片电阻-通用")
      (libsource (lib "Resistor") (part "R0603-2KF"))
    )
    (comp (ref "RT1")
      (value "10KF")
      (footprint "XU-GENARAL PCB :0402")
      (description "贴片电阻-通用")
      (libsource (lib "Resistor") (part "R0603-10KF"))
    )
    (comp (ref "S1")
      (value "KSMD6X6-4P")
      (footprint "PCB11:SW2-6*6H")
      (description "轻触按键")
      (libsource (lib "Key") (part "S-KSMD6X6-4P"))
    )
    (comp (ref "U1")
      (value "LM2901AVQPWR")
      (footprint "U-TSSOP14")
      (libsource (lib "IC") (part "LM2901AVQPWR"))
    )
    (comp (ref "U2")
      (value "LM2901AVQPWR")
      (footprint "U-TSSOP14")
      (libsource (lib "IC") (part "LM2901AVQPWR"))
    )
    (comp (ref "U3")
      (value "LM2901AVQPWR")
      (footprint "U-TSSOP14")
      (libsource (lib "IC") (part "LM2901AVQPWR"))
    )
    (comp (ref "U4") (value "NL27WZU04") (footprint "U-TSOP-6") (libsource (lib "IC") (part "NL27WZU04")))
    (comp (ref "U5") (value "CS8508E") (footprint "SO-8") (libsource (lib "PCB_Project_1") (part "CS8508E")))
    (comp (ref "U7")
      (value "AP6210")
      (footprint "AIWAC-bolster-V02:AP6210")
      (libsource (lib "IC") (part "AP6210"))
    )
    (comp (ref "U10") (value "PS7516") (footprint "U-SOT-23-6") (libsource (lib "IC") (part "PS7516")))
    (comp (ref "Y1")
      (value "26MHz")
      (footprint "Y-CPX-32GA-4P")
      (description "晶振-贴片无源")
      (libsource (lib "Others") (part "YC-26MHz"))
    )
  )
  (nets
    (net (code "1") (name "+vbs1_5V") (class "Default")
      (node (ref "C104") (pin "1") (pinfunction "1_1") (pintype "passive"))
      (node (ref "C105") (pin "2") (pinfunction "2_2") (pintype "passive"))
      (node (ref "J11") (pin "1") (pinfunction "VCC_1") (pintype "passive"))
      (node (ref "R103") (pin "2") (pinfunction "2_2") (pintype "passive"))
      (node (ref "U10") (pin "5") (pinfunction "OUT_5") (pintype "passive"))
    )
    (net (code "3") (name "/AP-CK32KO") (class "Default")
      (node (ref "M1") (pin "110") (pinfunction "AP-CK32KO_110") (pintype "passive"))
      (node (ref "R79") (pin "2") (pinfunction "2_2") (pintype "passive"))
      (node (ref "R80") (pin "2") (pinfunction "2_2") (pintype "passive"))
    )
    (net (code "4") (name "/AP-UART1-CTS") (class "Default")
      (node (ref "M1") (pin "38") (pinfunction "AP-UART1-CTS/PG9_38") (pintype "passive"))
      (node (ref "U7") (pin "41") (pinfunction "UART_RTS_N_41") (pintype "passive"))
    )
    (net (code "5") (name "/AP-UART1-RTS") (class "Default")
      (node (ref "M1") (pin "37") (pinfunction "AP-UART1-RTS/PG8_37") (pintype "passive"))
      (node (ref "U7") (pin "44") (pinfunction "UART_CTS_N_44") (pintype "passive"))
    )
    (net (code "6") (name "/AP-UART1-RX") (class "Default")
      (node (ref "M1") (pin "35") (pinfunction "AP-UART1-RX/PG7_35") (pintype "passive"))
      (node (ref "R72") (pin "2") (pinfunction "2_2") (pintype "passive"))
      (node (ref "U7") (pin "42") (pinfunction "UART_TXD_42") (pintype "passive"))
    )
    (net (code "7") (name "/AP-UART1-TX") (class "Default")
      (node (ref "M1") (pin "36") (pinfunction "AP-UART1-TX/PG6_36") (pintype "passive"))
      (node (ref "R73") (pin "2") (pinfunction "2_2") (pintype "passive"))
      (node (ref "U7") (pin "43") (pinfunction "UART_RXD_43") (pintype "passive"))
    )
    (net (code "8") (name "/BT-HOST-WAKE") (class "Default")
      (node (ref "M1") (pin "106") (pinfunction "BT-WAKE-AP/PL9_106") (pintype "passive"))
      (node (ref "U7") (pin "7") (pinfunction "BT_HOST_WAKE_7") (pintype "passive"))
    )
    (net (code "9") (name "/BT-RST-N") (class "Default")
      (node (ref "M1") (pin "109") (pinfunction "BT-RST-N/PL8_109") (pintype "passive"))
      (node (ref "R74") (pin "1") (pinfunction "1_1") (pintype "passive"))
      (node (ref "U7") (pin "34") (pinfunction "BT_RST_N_34") (pintype "passive"))
    )
    (net (code "10") (name "/BT-WAKE") (class "Default")
      (node (ref "M1") (pin "105") (pinfunction "AP-WAKE-BT/PL10_105") (pintype "passive"))
      (node (ref "R77") (pin "1") (pinfunction "1_1") (pintype "passive"))
      (node (ref "U7") (pin "6") (pinfunction "BT_WAKE_6") (pintype "passive"))
    )
    (net (code "11") (name "/CHGLED") (class "Default")
      (node (ref "M1") (pin "120") (pinfunction "CHGLED_120") (pintype "passive"))
      (node (ref "R83") (pin "2") (pinfunction "2_2") (pintype "passive"))
    )
    (net (code "12") (name "/HPL") (class "Default")
      (node (ref "C101") (pin "1") (pinfunction "1_1") (pintype "passive"))
      (node (ref "M1") (pin "118") (pinfunction "HPL_118") (pintype "passive"))
      (node (ref "R120") (pin "1") (pinfunction "1_1") (pintype "passive"))
    )
    (net (code "13") (name "/HPR") (class "Default")
      (node (ref "C100") (pin "1") (pinfunction "1_1") (pintype "passive"))
      (node (ref "M1") (pin "119") (pinfunction "HPR_119") (pintype "passive"))
    )
    (net (code "14") (name "/LRADC0") (class "Default")
      (node (ref "M1") (pin "115") (pinfunction "LRADC0_115") (pintype "passive"))
      (node (ref "R68") (pin "2") (pinfunction "2_2") (pintype "passive"))
      (node (ref "R69") (pin "1") (pinfunction "1_1") (pintype "passive"))
    )
    (net (code "15") (name "/Left-F") (class "Default")
      (node (ref "D2") (pin "1") (pinfunction "1_1") (pintype "passive"))
      (node (ref "M1") (pin "90") (pinfunction "LCD-D18_90") (pintype "passive"))
      (node (ref "R13") (pin "2") (pinfunction "2_2") (pintype "passive"))
    )
    (net (code "16") (name "/Left-H") (class "Default")
      (node (ref "D1") (pin "2") (pinfunction "2_2") (pintype "passive"))
      (node (ref "M1") (pin "94") (pinfunction "LCD-D12_94") (pintype "passive"))
      (node (ref "R9") (pin "2") (pinfunction "2_2") (pintype "passive"))
    )
    (net (code "17") (name "/Left-L") (class "Default")
      (node (ref "D4") (pin "2") (pinfunction "2_2") (pintype "passive"))
      (node (ref "M1") (pin "92") (pinfunction "LCD-D14_92") (pintype "passive"))
      (node (ref "R33") (pin "2") (pinfunction "2_2") (pintype "passive"))
    )
    (net (code "18") (name "/LeftF") (class "Default")
      (node (ref "C3") (pin "2") (pinfunction "2_2") (pintype "passive"))
      (node (ref "J3") (pin "6") (pinfunction "6_6") (pintype "passive"))
      (node (ref "R5") (pin "1") (pinfunction "1_1") (pintype "passive"))
      (node (ref "U1") (pin "8") (pinfunction "3IN-_8") (pintype "passive"))
    )
    (net (code "19") (name "/LeftH") (class "Default")
      (node (ref "C1") (pin "2") (pinfunction "2_2") (pintype "passive"))
      (node (ref "J3") (pin "2") (pinfunction "2_2") (pintype "passive"))
      (node (ref "R1") (pin "1") (pinfunction "1_1") (pintype "passive"))
      (node (ref "U1") (pin "6") (pinfunction "1IN-_6") (pintype "passive"))
    )
    (net (code "20") (name "/LeftL") (class "Default")
      (node (ref "C11") (pin "2") (pinfunction "2_2") (pintype "passive"))
      (node (ref "J4") (pin "2") (pinfunction "2_2") (pintype "passive"))
      (node (ref "R25") (pin "1") (pinfunction "1_1") (pintype "passive"))
      (node (ref "U2") (pin "6") (pinfunction "1IN-_6") (pintype "passive"))
    )
    (net (code "21") (name "/MCLK-IN") (class "Default")
      (node (ref "R63") (pin "1") (pinfunction "1_1") (pintype "passive"))
      (node (ref "U7") (pin "30") (pinfunction "TCXO_IN_30") (pintype "passive"))
    )
    (net (code "22") (name "/MIC+") (class "Default")
      (node (ref "C35") (pin "2") (pinfunction "2_2") (pintype "passive"))
      (node (ref "C38") (pin "1") (pinfunction "1_1") (pintype "passive"))
      (node (ref "J7") (pin "1") (pinfunction "1_1") (pintype "passive"))
      (node (ref "M1") (pin "116") (pinfunction "MIC+_116") (pintype "passive"))
      (node (ref "R110") (pin "1") (pinfunction "1_1") (pintype "passive"))
    )
    (net (code "23") (name "/MIC-") (class "Default")
      (node (ref "C38") (pin "2") (pinfunction "2_2") (pintype "passive"))
      (node (ref "C39") (pin "1") (pinfunction "1_1") (pintype "passive"))
      (node (ref "J7") (pin "2") (pinfunction "2_2") (pintype "passive"))
      (node (ref "M1") (pin "117") (pinfunction "MIC-_117") (pintype "passive"))
      (node (ref "R111") (pin "1") (pinfunction "1_1") (pintype "passive"))
    )
    (net (code "24") (name "/Mouth") (class "Default")
      (node (ref "C13") (pin "2") (pinfunction "2_2") (pintype "passive"))
      (node (ref "J4") (pin "6") (pinfunction "6_6") (pintype "passive"))
      (node (ref "R29") (pin "1") (pinfunction "1_1") (pintype "passive"))
      (node (ref "U2") (pin "8") (pinfunction "3IN-_8") (pintype "passive"))
    )
    (net (code "25") (name "/Mouth-T") (class "Default")
      (node (ref "D5") (pin "1") (pinfunction "1_1") (pintype "passive"))
      (node (ref "M1") (pin "97") (pinfunction "LCD-D7_97") (pintype "passive"))
      (node (ref "R37") (pin "2") (pinfunction "2_2") (pintype "passive"))
    )
    (net (code "26") (name "/PE0_CSI-PCLK") (class "Default")
      (node (ref "J1") (pin "7") (pinfunction "7_7") (pintype "passive"))
      (node (ref "M1") (pin "63") (pinfunction "PE0_CSI-PCLK_63") (pintype "passive"))
    )
    (net (code "27") (name "/PE1_CSI-MCLK") (class "Default")
      (node (ref "J1") (pin "11") (pinfunction "11_11") (pintype "passive"))
      (node (ref "M1") (pin "64") (pinfunction "PE1_CSI-MCLK_64") (pintype "passive"))
    )
    (net (code "28") (name "/PE2_CSI-HSYNC") (class "Default")
      (node (ref "J2") (pin "8") (pinfunction "8_8") (pintype "passive"))
      (node (ref "M1") (pin "65") (pinfunction "PE2_CSI-HSYNC_65") (pintype "passive"))
    )
    (net (code "29") (name "/PE3_CSI-VSYNC") (class "Default")
      (node (ref "J2") (pin "6") (pinfunction "6_6") (pintype "passive"))
      (node (ref "M1") (pin "66") (pinfunction "PE3_CSI-VSYNC_66") (pintype "passive"))
    )
    (net (code "30") (name "/PE4_CSI-D0") (class "Default")
      (node (ref "J1") (pin "5") (pinfunction "5_5") (pintype "passive"))
      (node (ref "M1") (pin "67") (pinfunction "PE4_CSI-D0_67") (pintype "passive"))
    )
    (net (code "31") (name "/PE5_CSI-D1") (class "Default")
      (node (ref "J1") (pin "3") (pinfunction "3_3") (pintype "passive"))
      (node (ref "M1") (pin "68") (pinfunction "PE5_CSI-D1_68") (pintype "passive"))
    )
    (net (code "32") (name "/PE6_CSI-D2") (class "Default")
      (node (ref "J1") (pin "2") (pinfunction "2_2") (pintype "passive"))
      (node (ref "M1") (pin "69") (pinfunction "PE6_CSI-D2_69") (pintype "passive"))
    )
    (net (code "33") (name "/PE7_CSI-D3") (class "Default")
      (node (ref "J1") (pin "4") (pinfunction "4_4") (pintype "passive"))
      (node (ref "M1") (pin "70") (pinfunction "PE7_CSI-D3_70") (pintype "passive"))
    )
    (net (code "34") (name "/PE8_CSI-D4") (class "Default")
      (node (ref "J1") (pin "6") (pinfunction "6_6") (pintype "passive"))
      (node (ref "M1") (pin "71") (pinfunction "PE8_CSI-D4_71") (pintype "passive"))
    )
    (net (code "35") (name "/PE9_CSI-D5") (class "Default")
      (node (ref "J1") (pin "8") (pinfunction "8_8") (pintype "passive"))
      (node (ref "M1") (pin "72") (pinfunction "PE9_CSI-D5_72") (pintype "passive"))
    )
    (net (code "36") (name "/PE10_CSI-D6") (class "Default")
      (node (ref "J1") (pin "10") (pinfunction "10_10") (pintype "passive"))
      (node (ref "M1") (pin "73") (pinfunction "PE10_CSI-D6_73") (pintype "passive"))
    )
    (net (code "37") (name "/PE11_CSI-D7") (class "Default")
      (node (ref "J2") (pin "11") (pinfunction "11_11") (pintype "passive"))
      (node (ref "M1") (pin "74") (pinfunction "PE11_CSI-D7_74") (pintype "passive"))
    )
    (net (code "38") (name "/PE12_CSI-SCK") (class "Default")
      (node (ref "J2") (pin "4") (pinfunction "4_4") (pintype "passive"))
      (node (ref "M1") (pin "75") (pinfunction "PE12_CSI-SCK_75") (pintype "passive"))
    )
    (net (code "39") (name "/PE13_CSI-SDA") (class "Default")
      (node (ref "J2") (pin "2") (pinfunction "2_2") (pintype "passive"))
      (node (ref "M1") (pin "76") (pinfunction "PE13_CSI-SDA_76") (pintype "passive"))
    )
    (net (code "40") (name "/PE16_CSI-RST-F") (class "Default")
      (node (ref "J2") (pin "5") (pinfunction "5_5") (pintype "passive"))
      (node (ref "M1") (pin "79") (pinfunction "PE16_CSI-RST-F_79") (pintype "passive"))
      (node (ref "R50") (pin "2") (pinfunction "2_2") (pintype "passive"))
    )
    (net (code "41") (name "/PE17_CSI-STBY-F") (class "Default")
      (node (ref "J2") (pin "7") (pinfunction "7_7") (pintype "passive"))
      (node (ref "M1") (pin "80") (pinfunction "PE17_CSI-STBY-F_80") (pintype "passive"))
      (node (ref "R39") (pin "1") (pinfunction "1_1") (pintype "passive"))
    )
    (net (code "42") (name "/POWERKEY") (class "Default")
      (node (ref "M1") (pin "14") (pinfunction "POWERKEY_14") (pintype "passive"))
      (node (ref "S1") (pin "2") (pinfunction "2_2") (pintype "passive"))
    )
    (net (code "43") (name "/Reference_R1") (class "Default")
      (node (ref "C8") (pin "1") (pinfunction "1_1") (pintype "passive"))
      (node (ref "R16") (pin "2") (pinfunction "2_2") (pintype "passive"))
      (node (ref "R20") (pin "2") (pinfunction "2_2") (pintype "passive"))
      (node (ref "R22") (pin "2") (pinfunction "2_2") (pintype "passive"))
      (node (ref "U1") (pin "11") (pinfunction "4IN+_11") (pintype "passive"))
    )
    (net (code "44") (name "/Right-F") (class "Default")
      (node (ref "D2") (pin "2") (pinfunction "2_2") (pintype "passive"))
      (node (ref "M1") (pin "89") (pinfunction "LCD-D19_89") (pintype "passive"))
      (node (ref "R14") (pin "2") (pinfunction "2_2") (pintype "passive"))
    )
    (net (code "45") (name "/Right-H") (class "Default")
      (node (ref "D1") (pin "1") (pinfunction "1_1") (pintype "passive"))
      (node (ref "M1") (pin "93") (pinfunction "LCD-D13_93") (pintype "passive"))
      (node (ref "R10") (pin "2") (pinfunction "2_2") (pintype "passive"))
    )
    (net (code "46") (name "/Right-L") (class "Default")
      (node (ref "D4") (pin "1") (pinfunction "1_1") (pintype "passive"))
      (node (ref "M1") (pin "91") (pinfunction "LCD-D15_91") (pintype "passive"))
      (node (ref "R34") (pin "2") (pinfunction "2_2") (pintype "passive"))
    )
    (net (code "47") (name "/RightF") (class "Default")
      (node (ref "C4") (pin "2") (pinfunction "2_2") (pintype "passive"))
      (node (ref "J3") (pin "8") (pinfunction "8_8") (pintype "passive"))
      (node (ref "R6") (pin "1") (pinfunction "1_1") (pintype "passive"))
      (node (ref "U1") (pin "10") (pinfunction "4IN-_10") (pintype "passive"))
    )
    (net (code "48") (name "/RightH") (class "Default")
      (node (ref "C2") (pin "2") (pinfunction "2_2") (pintype "passive"))
      (node (ref "J3") (pin "4") (pinfunction "4_4") (pintype "passive"))
      (node (ref "R2") (pin "1") (pinfunction "1_1") (pintype "passive"))
      (node (ref "U1") (pin "4") (pinfunction "2IN-_4") (pintype "passive"))
    )
    (net (code "49") (name "/RightL") (class "Default")
      (node (ref "C12") (pin "2") (pinfunction "2_2") (pintype "passive"))
      (node (ref "J4") (pin "4") (pinfunction "4_4") (pintype "passive"))
      (node (ref "R26") (pin "1") (pinfunction "1_1") (pintype "passive"))
      (node (ref "U2") (pin "4") (pinfunction "2IN-_4") (pintype "passive"))
    )
    (net (code "50") (name "/SDC0-CLK") (class "Default")
      (node (ref "J9") (pin "6") (pinfunction "CLK_6") (pintype "passive"))
      (node (ref "M1") (pin "58") (pinfunction "SDC0-CLK/UART0-TX/PF2_58") (pintype "passive"))
    )
    (net (code "51") (name "/SDC0-CMD") (class "Default")
      (node (ref "J9") (pin "4") (pinfunction "CMD_4") (pintype "power_in"))
      (node (ref "M1") (pin "57") (pinfunction "SDC0-CMD/PF3_57") (pintype "passive"))
    )
    (net (code "52") (name "/SDC0-D0") (class "Default")
      (node (ref "J9") (pin "8") (pinfunction "DAT0_8") (pintype "passive"))
      (node (ref "M1") (pin "53") (pinfunction "SDC0-D0/PF1_53") (pintype "passive"))
    )
    (net (code "53") (name "/SDC0-D1") (class "Default")
      (node (ref "J9") (pin "9") (pinfunction "DAT1_9") (pintype "passive"))
      (node (ref "M1") (pin "54") (pinfunction "SDC0-D1/PF0_54") (pintype "passive"))
    )
    (net (code "54") (name "/SDC0-D2") (class "Default")
      (node (ref "J9") (pin "2") (pinfunction "DAT2_2") (pintype "power_in"))
      (node (ref "M1") (pin "55") (pinfunction "SDC0-D2/PF5_55") (pintype "passive"))
    )
    (net (code "55") (name "/SDC0-D3") (class "Default")
      (node (ref "J9") (pin "3") (pinfunction "DAT3_3") (pintype "power_in"))
      (node (ref "M1") (pin "56") (pinfunction "SDC0-D3/UART0-RX/PF4_56") (pintype "passive"))
    )
    (net (code "56") (name "/SDIO-CLK") (class "Default")
      (node (ref "M1") (pin "42") (pinfunction "WL-SDIO-CLK/PG0_42") (pintype "passive"))
      (node (ref "R84") (pin "2") (pinfunction "2_2") (pintype "passive"))
    )
    (net (code "57") (name "/SDIO-CMD") (class "Default")
      (node (ref "M1") (pin "41") (pinfunction "WL-SDIO-CMD/PG1_41") (pintype "passive"))
      (node (ref "R89") (pin "2") (pinfunction "2_2") (pintype "passive"))
      (node (ref "U7") (pin "16") (pinfunction "SDIO_DATA_CMD_16") (pintype "passive"))
    )
    (net (code "58") (name "/SDIO-D0") (class "Default")
      (node (ref "M1") (pin "43") (pinfunction "WL-SDIO-D0/PG2_43") (pintype "passive"))
      (node (ref "R90") (pin "2") (pinfunction "2_2") (pintype "passive"))
      (node (ref "U7") (pin "18") (pinfunction "SDIO_DATA_0_18") (pintype "passive"))
    )
    (net (code "59") (name "/SDIO-D1") (class "Default")
      (node (ref "M1") (pin "44") (pinfunction "WL-SDIO-D1/PG3_44") (pintype "passive"))
      (node (ref "R91") (pin "2") (pinfunction "2_2") (pintype "passive"))
      (node (ref "U7") (pin "19") (pinfunction "SDIO_DATA_1_19") (pintype "passive"))
    )
    (net (code "60") (name "/SDIO-D2") (class "Default")
      (node (ref "M1") (pin "45") (pinfunction "WL-SDIO-D2/PG4_45") (pintype "passive"))
      (node (ref "R87") (pin "2") (pinfunction "2_2") (pintype "passive"))
      (node (ref "U7") (pin "14") (pinfunction "SDIO_DATA_2_14") (pintype "passive"))
    )
    (net (code "61") (name "/SDIO-D3") (class "Default")
      (node (ref "M1") (pin "46") (pinfunction "WL-SDIO-D3/PG5_46") (pintype "passive"))
      (node (ref "R88") (pin "2") (pinfunction "2_2") (pintype "passive"))
      (node (ref "U7") (pin "15") (pinfunction "SDIO_DATA_3_15") (pintype "passive"))
    )
    (net (code "62") (name "/T-CARD-DET") (class "Default")
      (node (ref "J9") (pin "10") (pinfunction "CD#_10") (pintype "passive"))
      (node (ref "M1") (pin "52") (pinfunction "T-CARD-DET/PB4_52") (pintype "passive"))
    )
    (net (code "63") (name "/Temp") (class "Default")
      (node (ref "C50") (pin "1") (pinfunction "1_1") (pintype "passive"))
      (node (ref "M1") (pin "5") (pinfunction "TS_5") (pintype "passive"))
      (node (ref "R76") (pin "2") (pinfunction "2_2") (pintype "passive"))
      (node (ref "RT1") (pin "1") (pinfunction "1_1") (pintype "passive"))
    )
    (net (code "64") (name "/Touch-INT") (class "Default")
      (node (ref "M1") (pin "34") (pinfunction "TP-INT/PB5_34") (pintype "passive"))
      (node (ref "R56") (pin "2") (pinfunction "2_2") (pintype "passive"))
    )
    (net (code "65") (name "/Tummy") (class "Default")
      (node (ref "C14") (pin "2") (pinfunction "2_2") (pintype "passive"))
      (node (ref "C21") (pin "2") (pinfunction "2_2") (pintype "passive"))
      (node (ref "J4") (pin "8") (pinfunction "8_8") (pintype "passive"))
      (node (ref "R30") (pin "1") (pinfunction "1_1") (pintype "passive"))
      (node (ref "R51") (pin "1") (pinfunction "1_1") (pintype "passive"))
      (node (ref "U2") (pin "10") (pinfunction "4IN-_10") (pintype "passive"))
      (node (ref "U3") (pin "6") (pinfunction "1IN-_6") (pintype "passive"))
    )
    (net (code "66") (name "/Tummy1") (class "Default")
      (node (ref "D5") (pin "2") (pinfunction "2_2") (pintype "passive"))
      (node (ref "M1") (pin "96") (pinfunction "LCD-D10_96") (pintype "passive"))
      (node (ref "R38") (pin "2") (pinfunction "2_2") (pintype "passive"))
    )
    (net (code "67") (name "/Tummy2") (class "Default")
      (node (ref "M1") (pin "95") (pinfunction "LCD-D11_95") (pintype "passive"))
      (node (ref "R55") (pin "2") (pinfunction "2_2") (pintype "passive"))
    )
    (net (code "68") (name "/USB-DM0") (class "Default")
      (node (ref "D22") (pin "2") (pinfunction "K_2") (pintype "passive"))
      (node (ref "J10") (pin "2") (pinfunction "D-_2") (pintype "passive"))
      (node (ref "M1") (pin "113") (pinfunction "USB-DM0_113") (pintype "passive"))
    )
    (net (code "69") (name "/USB-DM1") (class "Default")
      (node (ref "D11") (pin "2") (pinfunction "K_2") (pintype "passive"))
      (node (ref "J11") (pin "2") (pinfunction "D-_2") (pintype "passive"))
      (node (ref "R110") (pin "2") (pinfunction "2_2") (pintype "passive"))
      (node (ref "R113") (pin "2") (pinfunction "2_2") (pintype "passive"))
    )
    (net (code "70") (name "/USB-DP0") (class "Default")
      (node (ref "D21") (pin "2") (pinfunction "K_2") (pintype "passive"))
      (node (ref "J10") (pin "3") (pinfunction "D+_3") (pintype "passive"))
      (node (ref "M1") (pin "114") (pinfunction "USB-DP0_114") (pintype "passive"))
    )
    (net (code "71") (name "/USB-DP1") (class "Default")
      (node (ref "D12") (pin "2") (pinfunction "K_2") (pintype "passive"))
      (node (ref "J11") (pin "3") (pinfunction "D+_3") (pintype "passive"))
      (node (ref "R111") (pin "2") (pinfunction "2_2") (pintype "passive"))
      (node (ref "R112") (pin "2") (pinfunction "2_2") (pintype "passive"))
    )
    (net (code "72") (name "/USB-DRVVBUS") (class "Default")
      (node (ref "M1") (pin "21") (pinfunction "USB-DRVVBUS_21") (pintype "passive"))
    )
    (net (code "73") (name "/USB-ID") (class "Default")
      (node (ref "M1") (pin "29") (pinfunction "USB-ID/PH8_29") (pintype "passive"))
      (node (ref "R70") (pin "1") (pinfunction "1_1") (pintype "passive"))
    )
    (net (code "74") (name "/WL-HOST-WAKE") (class "Default")
      (node (ref "M1") (pin "108") (pinfunction "WL-WAKE-AP/PL7_108") (pintype "passive"))
      (node (ref "U7") (pin "13") (pinfunction "WL_HOST_WAKE_13") (pintype "passive"))
    )
    (net (code "75") (name "/WL-REG-ON") (class "Default")
      (node (ref "M1") (pin "107") (pinfunction "WL-PMU-EN/PL6_107") (pintype "passive"))
      (node (ref "R82") (pin "1") (pinfunction "1_1") (pintype "passive"))
      (node (ref "U7") (pin "12") (pinfunction "WL_REG_ON_12") (pintype "passive"))
    )
    (net (code "76") (name "AVDD-CSI") (class "Default")
      (node (ref "C29") (pin "1") (pinfunction "1_1") (pintype "passive"))
      (node (ref "J2") (pin "3") (pinfunction "3_3") (pintype "passive"))
      (node (ref "M1") (pin "8") (pinfunction "AVDD-CSI_8") (pintype "passive"))
    )
    (net (code "77") (name "DOVDD-CSI") (class "Default")
      (node (ref "C23") (pin "1") (pinfunction "1_1") (pintype "passive"))
      (node (ref "C24") (pin "1") (pinfunction "1_1") (pintype "passive"))
      (node (ref "C25") (pin "1") (pinfunction "1_1") (pintype "passive"))
      (node (ref "J2") (pin "10") (pinfunction "10_10") (pintype "passive"))
      (node (ref "M1") (pin "2") (pinfunction "DOVDD-CSI_2") (pintype "passive"))
      (node (ref "R39") (pin "2") (pinfunction "2_2") (pintype "passive"))
      (node (ref "R50") (pin "1") (pinfunction "1_1") (pintype "passive"))
    )
    (net (code "78") (name "DVDD1V8-CSI") (class "Default")
      (node (ref "C28") (pin "1") (pinfunction "1_1") (pintype "passive"))
      (node (ref "J2") (pin "9") (pinfunction "9_9") (pintype "passive"))
      (node (ref "M1") (pin "13") (pinfunction "DVDD1V8-CSI_13") (pintype "passive"))
    )
    (net (code "79") (name "GND") (class "Default")
      (node (ref "ANT1") (pin "2") (pinfunction "2_2") (pintype "passive"))
      (node (ref "ANT1") (pin "3") (pinfunction "3_3") (pintype "passive"))
      (node (ref "C1") (pin "1") (pinfunction "1_1") (pintype "passive"))
      (node (ref "C10") (pin "2") (pinfunction "2_2") (pintype "passive"))
      (node (ref "C102") (pin "2") (pinfunction "2_2") (pintype "passive"))
      (node (ref "C103") (pin "1") (pinfunction "1_1") (pintype "passive"))
      (node (ref "C104") (pin "2") (pinfunction "2_2") (pintype "passive"))
      (node (ref "C105") (pin "1") (pinfunction "1_1") (pintype "passive"))
      (node (ref "C11") (pin "1") (pinfunction "1_1") (pintype "passive"))
      (node (ref "C110") (pin "2") (pinfunction "2_2") (pintype "passive"))
      (node (ref "C12") (pin "1") (pinfunction "1_1") (pintype "passive"))
      (node (ref "C13") (pin "1") (pinfunction "1_1") (pintype "passive"))
      (node (ref "C14") (pin "1") (pinfunction "1_1") (pintype "passive"))
      (node (ref "C15") (pin "2") (pinfunction "2_2") (pintype "passive"))
      (node (ref "C16") (pin "2") (pinfunction "2_2") (pintype "passive"))
      (node (ref "C17") (pin "2") (pinfunction "2_2") (pintype "passive"))
      (node (ref "C18") (pin "2") (pinfunction "2_2") (pintype "passive"))
      (node (ref "C19") (pin "1") (pinfunction "1_1") (pintype "passive"))
      (node (ref "C2") (pin "1") (pinfunction "1_1") (pintype "passive"))
      (node (ref "C20") (pin "2") (pinfunction "2_2") (pintype "passive"))
      (node (ref "C21") (pin "1") (pinfunction "1_1") (pintype "passive"))
      (node (ref "C22") (pin "1") (pinfunction "1_1") (pintype "passive"))
      (node (ref "C23") (pin "2") (pinfunction "2_2") (pintype "passive"))
      (node (ref "C24") (pin "2") (pinfunction "2_2") (pintype "passive"))
      (node (ref "C25") (pin "2") (pinfunction "2_2") (pintype "passive"))
      (node (ref "C26") (pin "2") (pinfunction "2_2") (pintype "passive"))
      (node (ref "C27") (pin "2") (pinfunction "2_2") (pintype "passive"))
      (node (ref "C28") (pin "2") (pinfunction "2_2") (pintype "passive"))
      (node (ref "C29") (pin "2") (pinfunction "2_2") (pintype "passive"))
      (node (ref "C3") (pin "1") (pinfunction "1_1") (pintype "passive"))
      (node (ref "C30") (pin "1") (pinfunction "1_1") (pintype "passive"))
      (node (ref "C31") (pin "2") (pinfunction "2_2") (pintype "passive"))
      (node (ref "C32") (pin "1") (pinfunction "1_1") (pintype "passive"))
      (node (ref "C33") (pin "1") (pinfunction "1_1") (pintype "passive"))
      (node (ref "C34") (pin "2") (pinfunction "2_2") (pintype "passive"))
      (node (ref "C35") (pin "1") (pinfunction "1_1") (pintype "passive"))
      (node (ref "C36") (pin "2") (pinfunction "2_2") (pintype "passive"))
      (node (ref "C37") (pin "1") (pinfunction "1_1") (pintype "passive"))
      (node (ref "C39") (pin "2") (pinfunction "2_2") (pintype "passive"))
      (node (ref "C4") (pin "1") (pinfunction "1_1") (pintype "passive"))
      (node (ref "C40") (pin "2") (pinfunction "2_2") (pintype "passive"))
      (node (ref "C41") (pin "2") (pinfunction "2_2") (pintype "passive"))
      (node (ref "C42") (pin "2") (pinfunction "2_2") (pintype "passive"))
      (node (ref "C43") (pin "2") (pinfunction "2_2") (pintype "passive"))
      (node (ref "C44") (pin "1") (pinfunction "1_1") (pintype "passive"))
      (node (ref "C45") (pin "2") (pinfunction "2_2") (pintype "passive"))
      (node (ref "C47") (pin "1") (pinfunction "1_1") (pintype "passive"))
      (node (ref "C48") (pin "1") (pinfunction "1_1") (pintype "passive"))
      (node (ref "C5") (pin "2") (pinfunction "2_2") (pintype "passive"))
      (node (ref "C50") (pin "2") (pinfunction "2_2") (pintype "passive"))
      (node (ref "C51") (pin "2") (pinfunction "2_2") (pintype "passive"))
      (node (ref "C55") (pin "1") (pinfunction "1_1") (pintype "passive"))
      (node (ref "C56") (pin "1") (pinfunction "1_1") (pintype "passive"))
      (node (ref "C57") (pin "2") (pinfunction "2_2") (pintype "passive"))
      (node (ref "C6") (pin "2") (pinfunction "2_2") (pintype "passive"))
      (node (ref "C7") (pin "2") (pinfunction "2_2") (pintype "passive"))
      (node (ref "C8") (pin "2") (pinfunction "2_2") (pintype "passive"))
      (node (ref "C9") (pin "1") (pinfunction "1_1") (pintype "passive"))
      (node (ref "D11") (pin "1") (pinfunction "A_1") (pintype "passive"))
      (node (ref "D12") (pin "1") (pinfunction "A_1") (pintype "passive"))
      (node (ref "D21") (pin "1") (pinfunction "A_1") (pintype "passive"))
      (node (ref "D22") (pin "1") (pinfunction "A_1") (pintype "passive"))
      (node (ref "D3") (pin "2") (pinfunction "2_2") (pintype "passive"))
      (node (ref "D7") (pin "K") (pintype "passive"))
      (node (ref "J1") (pin "1") (pinfunction "1_1") (pintype "passive"))
      (node (ref "J1") (pin "12") (pinfunction "12_12") (pintype "passive"))
      (node (ref "J1") (pin "13") (pinfunction "13_13") (pintype "passive"))
      (node (ref "J1") (pin "14") (pinfunction "14_14") (pintype "passive"))
      (node (ref "J1") (pin "9") (pinfunction "9_9") (pintype "passive"))
      (node (ref "J10") (pin "10") (pinfunction "SHELL_10") (pintype "passive"))
      (node (ref "J10") (pin "5") (pinfunction "GND_5") (pintype "passive"))
      (node (ref "J10") (pin "6") (pinfunction "SHELL_6") (pintype "passive"))
      (node (ref "J10") (pin "7") (pinfunction "SHELL_7") (pintype "passive"))
      (node (ref "J10") (pin "8") (pinfunction "SHELL_8") (pintype "passive"))
      (node (ref "J10") (pin "9") (pinfunction "SHELL_9") (pintype "passive"))
      (node (ref "J11") (pin "10") (pinfunction "SHELL_10") (pintype "passive"))
      (node (ref "J11") (pin "5") (pinfunction "GND_5") (pintype "passive"))
      (node (ref "J11") (pin "6") (pinfunction "SHELL_6") (pintype "passive"))
      (node (ref "J11") (pin "7") (pinfunction "SHELL_7") (pintype "passive"))
      (node (ref "J11") (pin "8") (pinfunction "SHELL_8") (pintype "passive"))
      (node (ref "J11") (pin "9") (pinfunction "SHELL_9") (pintype "passive"))
      (node (ref "J2") (pin "1") (pinfunction "1_1") (pintype "passive"))
      (node (ref "J2") (pin "12") (pinfunction "12_12") (pintype "passive"))
      (node (ref "J2") (pin "13") (pinfunction "13_13") (pintype "passive"))
      (node (ref "J2") (pin "14") (pinfunction "14_14") (pintype "passive"))
      (node (ref "J3") (pin "1") (pinfunction "1_1") (pintype "passive"))
      (node (ref "J3") (pin "10") (pinfunction "10_10") (pintype "passive"))
      (node (ref "J3") (pin "3") (pinfunction "3_3") (pintype "passive"))
      (node (ref "J3") (pin "5") (pinfunction "5_5") (pintype "passive"))
      (node (ref "J3") (pin "7") (pinfunction "7_7") (pintype "passive"))
      (node (ref "J3") (pin "9") (pinfunction "9_9") (pintype "passive"))
      (node (ref "J4") (pin "1") (pinfunction "1_1") (pintype "passive"))
      (node (ref "J4") (pin "10") (pinfunction "10_10") (pintype "passive"))
      (node (ref "J4") (pin "3") (pinfunction "3_3") (pintype "passive"))
      (node (ref "J4") (pin "5") (pinfunction "5_5") (pintype "passive"))
      (node (ref "J4") (pin "7") (pinfunction "7_7") (pintype "passive"))
      (node (ref "J4") (pin "9") (pinfunction "9_9") (pintype "passive"))
      (node (ref "J6") (pin "3") (pinfunction "3_3") (pintype "passive"))
      (node (ref "J6") (pin "4") (pinfunction "4_4") (pintype "passive"))
      (node (ref "J7") (pin "3") (pinfunction "3_3") (pintype "passive"))
      (node (ref "J7") (pin "4") (pinfunction "4_4") (pintype "passive"))
      (node (ref "J8") (pin "2") (pinfunction "2_2") (pintype "passive"))
      (node (ref "J9") (pin "11") (pinfunction "GND_11") (pintype "passive"))
      (node (ref "J9") (pin "12") (pinfunction "GND_12") (pintype "passive"))
      (node (ref "J9") (pin "7") (pinfunction "VSS2_7") (pintype "passive"))
      (node (ref "M1") (pin "103") (pinfunction "GND_103") (pintype "passive"))
      (node (ref "M1") (pin "121") (pinfunction "GND_121") (pintype "passive"))
      (node (ref "M1") (pin "122") (pinfunction "GND_122") (pintype "passive"))
      (node (ref "M1") (pin "123") (pinfunction "GND_123") (pintype "passive"))
      (node (ref "M1") (pin "124") (pinfunction "GND_124") (pintype "passive"))
      (node (ref "M1") (pin "40") (pinfunction "GND_40") (pintype "passive"))
      (node (ref "M1") (pin "51") (pinfunction "GND_51") (pintype "passive"))
      (node (ref "M1") (pin "9") (pinfunction "GND_9") (pintype "passive"))
      (node (ref "R102") (pin "1") (pinfunction "1_1") (pintype "passive"))
      (node (ref "R104") (pin "1") (pinfunction "1_1") (pintype "passive"))
      (node (ref "R21") (pin "1") (pinfunction "1_1") (pintype "passive"))
      (node (ref "R22") (pin "1") (pinfunction "1_1") (pintype "passive"))
      (node (ref "R23") (pin "1") (pinfunction "1_1") (pintype "passive"))
      (node (ref "R24") (pin "1") (pinfunction "1_1") (pintype "passive"))
      (node (ref "R45") (pin "1") (pinfunction "1_1") (pintype "passive"))
      (node (ref "R47") (pin "1") (pinfunction "1_1") (pintype "passive"))
      (node (ref "R48") (pin "1") (pinfunction "1_1") (pintype "passive"))
      (node (ref "R49") (pin "1") (pinfunction "1_1") (pintype "passive"))
      (node (ref "R52") (pin "1") (pinfunction "1_1") (pintype "passive"))
      (node (ref "R59") (pin "1") (pinfunction "1_1") (pintype "passive"))
      (node (ref "R61") (pin "1") (pinfunction "1_1") (pintype "passive"))
      (node (ref "R74") (pin "2") (pinfunction "2_2") (pintype "passive"))
      (node (ref "R76") (pin "1") (pinfunction "1_1") (pintype "passive"))
      (node (ref "R77") (pin "2") (pinfunction "2_2") (pintype "passive"))
      (node (ref "R82") (pin "2") (pinfunction "2_2") (pintype "passive"))
      (node (ref "S1") (pin "1") (pinfunction "1_1") (pintype "passive"))
      (node (ref "U1") (pin "12") (pinfunction "GND_12") (pintype "passive"))
      (node (ref "U10") (pin "2") (pinfunction "GND_2") (pintype "passive"))
      (node (ref "U2") (pin "12") (pinfunction "GND_12") (pintype "passive"))
      (node (ref "U3") (pin "12") (pinfunction "GND_12") (pintype "passive"))
      (node (ref "U4") (pin "2") (pinfunction "GND_2") (pintype "passive"))
      (node (ref "U5") (pin "8") (pinfunction "GND_8") (pintype "passive"))
      (node (ref "U7") (pin "1") (pinfunction "GND_1") (pintype "passive"))
      (node (ref "U7") (pin "20") (pinfunction "GND_20") (pintype "passive"))
      (node (ref "U7") (pin "3") (pinfunction "GND_3") (pintype "passive"))
      (node (ref "U7") (pin "31") (pinfunction "GND_31") (pintype "passive"))
      (node (ref "U7") (pin "33") (pinfunction "GND_33") (pintype "passive"))
      (node (ref "U7") (pin "36") (pinfunction "GND_36") (pintype "passive"))
      (node (ref "Y1") (pin "2") (pinfunction "GND_2") (pintype "passive"))
      (node (ref "Y1") (pin "4") (pinfunction "GND_4") (pintype "passive"))
    )
    (net (code "80") (name "Net-(ANT1-W)") (class "Default")
      (node (ref "ANT1") (pin "1") (pinfunction "W_1") (pintype "passive"))
      (node (ref "C47") (pin "2") (pinfunction "2_2") (pintype "passive"))
      (node (ref "C49") (pin "2") (pinfunction "2_2") (pintype "passive"))
    )
    (net (code "81") (name "Net-(C36-Pad1)") (class "Default")
      (node (ref "C36") (pin "1") (pinfunction "1_1") (pintype "passive"))
      (node (ref "J6") (pin "2") (pinfunction "2_2") (pintype "passive"))
      (node (ref "L3") (pin "1") (pinfunction "1_1") (pintype "passive"))
    )
    (net (code "82") (name "Net-(C40-Pad1)") (class "Default")
      (node (ref "C40") (pin "1") (pinfunction "1_1") (pintype "passive"))
      (node (ref "J6") (pin "1") (pinfunction "1_1") (pintype "passive"))
      (node (ref "L4") (pin "1") (pinfunction "1_1") (pintype "passive"))
    )
    (net (code "83") (name "Net-(C100-Pad2)") (class "Default")
      (node (ref "C100") (pin "2") (pinfunction "2_2") (pintype "passive"))
      (node (ref "R66") (pin "1") (pinfunction "1_1") (pintype "passive"))
    )
    (net (code "84") (name "Net-(C101-Pad2)") (class "Default")
      (node (ref "C101") (pin "2") (pinfunction "2_2") (pintype "passive"))
      (node (ref "R67") (pin "1") (pinfunction "1_1") (pintype "passive"))
    )
    (net (code "85") (name "Net-(D6-PadK)") (class "Default")
      (node (ref "D6") (pin "K") (pintype "passive"))
      (node (ref "R83") (pin "1") (pinfunction "1_1") (pintype "passive"))
    )
    (net (code "86") (name "Net-(D7-PadA)") (class "Default")
      (node (ref "D7") (pin "A") (pintype "passive"))
      (node (ref "R92") (pin "1") (pinfunction "1_1") (pintype "passive"))
    )
    (net (code "87") (name "Net-(J9-Voice_Key)") (class "Default")
      (node (ref "J9") (pin "1") (pinfunction "Voice_Key_1") (pintype "passive"))
      (node (ref "R69") (pin "2") (pinfunction "2_2") (pintype "passive"))
    )
    (net (code "88") (name "Net-(J10-ID)") (class "Default")
      (node (ref "J10") (pin "4") (pinfunction "ID_4") (pintype "passive"))
      (node (ref "R70") (pin "2") (pinfunction "2_2") (pintype "passive"))
      (node (ref "R71") (pin "1") (pinfunction "1_1") (pintype "passive"))
    )
    (net (code "89") (name "Net-(J11-ID)") (class "Default")
      (node (ref "J11") (pin "4") (pinfunction "ID_4") (pintype "passive"))
      (node (ref "R120") (pin "2") (pinfunction "2_2") (pintype "passive"))
    )
    (net (code "90") (name "Net-(M1-USB-DM1)") (class "Default")
      (node (ref "M1") (pin "111") (pinfunction "USB-DM1_111") (pintype "passive"))
      (node (ref "R113") (pin "1") (pinfunction "1_1") (pintype "passive"))
    )
    (net (code "91") (name "Net-(M1-USB-DP1)") (class "Default")
      (node (ref "M1") (pin "112") (pinfunction "USB-DP1_112") (pintype "passive"))
      (node (ref "R112") (pin "1") (pinfunction "1_1") (pintype "passive"))
    )
    (net (code "92") (name "Net-(U1A-1IN+)") (class "Default")
      (node (ref "C5") (pin "1") (pinfunction "1_1") (pintype "passive"))
      (node (ref "R11") (pin "2") (pinfunction "2_2") (pintype "passive"))
      (node (ref "R18") (pin "2") (pinfunction "2_2") (pintype "passive"))
      (node (ref "R23") (pin "2") (pinfunction "2_2") (pintype "passive"))
      (node (ref "U1") (pin "7") (pinfunction "1IN+_7") (pintype "passive"))
    )
    (net (code "93") (name "Net-(U1A-1OUT)") (class "Default")
      (node (ref "R18") (pin "1") (pinfunction "1_1") (pintype "passive"))
      (node (ref "R3") (pin "1") (pinfunction "1_1") (pintype "passive"))
      (node (ref "R9") (pin "1") (pinfunction "1_1") (pintype "passive"))
      (node (ref "U1") (pin "1") (pinfunction "1OUT_1") (pintype "passive"))
    )
    (net (code "94") (name "Net-(U1B-2IN+)") (class "Default")
      (node (ref "C6") (pin "1") (pinfunction "1_1") (pintype "passive"))
      (node (ref "R12") (pin "2") (pinfunction "2_2") (pintype "passive"))
      (node (ref "R17") (pin "2") (pinfunction "2_2") (pintype "passive"))
      (node (ref "R21") (pin "2") (pinfunction "2_2") (pintype "passive"))
      (node (ref "U1") (pin "5") (pinfunction "2IN+_5") (pintype "passive"))
    )
    (net (code "95") (name "Net-(U1B-2OUT)") (class "Default")
      (node (ref "R10") (pin "1") (pinfunction "1_1") (pintype "passive"))
      (node (ref "R17") (pin "1") (pinfunction "1_1") (pintype "passive"))
      (node (ref "R4") (pin "1") (pinfunction "1_1") (pintype "passive"))
      (node (ref "U1") (pin "2") (pinfunction "2OUT_2") (pintype "passive"))
    )
    (net (code "96") (name "Net-(U1C-3IN+)") (class "Default")
      (node (ref "C7") (pin "1") (pinfunction "1_1") (pintype "passive"))
      (node (ref "R15") (pin "2") (pinfunction "2_2") (pintype "passive"))
      (node (ref "R19") (pin "2") (pinfunction "2_2") (pintype "passive"))
      (node (ref "R24") (pin "2") (pinfunction "2_2") (pintype "passive"))
      (node (ref "U1") (pin "9") (pinfunction "3IN+_9") (pintype "passive"))
    )
    (net (code "97") (name "Net-(U1C-3OUT)") (class "Default")
      (node (ref "R13") (pin "1") (pinfunction "1_1") (pintype "passive"))
      (node (ref "R19") (pin "1") (pinfunction "1_1") (pintype "passive"))
      (node (ref "R7") (pin "1") (pinfunction "1_1") (pintype "passive"))
      (node (ref "U1") (pin "14") (pinfunction "3OUT_14") (pintype "passive"))
    )
    (net (code "98") (name "Net-(U1D-4OUT)") (class "Default")
      (node (ref "R14") (pin "1") (pinfunction "1_1") (pintype "passive"))
      (node (ref "R20") (pin "1") (pinfunction "1_1") (pintype "passive"))
      (node (ref "R8") (pin "1") (pinfunction "1_1") (pintype "passive"))
      (node (ref "U1") (pin "13") (pinfunction "4OUT_13") (pintype "passive"))
    )
    (net (code "99") (name "Net-(U2A-1IN+)") (class "Default")
      (node (ref "C15") (pin "1") (pinfunction "1_1") (pintype "passive"))
      (node (ref "R35") (pin "2") (pinfunction "2_2") (pintype "passive"))
      (node (ref "R46") (pin "2") (pinfunction "2_2") (pintype "passive"))
      (node (ref "R49") (pin "2") (pinfunction "2_2") (pintype "passive"))
      (node (ref "U2") (pin "7") (pinfunction "1IN+_7") (pintype "passive"))
    )
    (net (code "100") (name "Net-(U2A-1OUT)") (class "Default")
      (node (ref "R27") (pin "1") (pinfunction "1_1") (pintype "passive"))
      (node (ref "R33") (pin "1") (pinfunction "1_1") (pintype "passive"))
      (node (ref "R46") (pin "1") (pinfunction "1_1") (pintype "passive"))
      (node (ref "U2") (pin "1") (pinfunction "1OUT_1") (pintype "passive"))
    )
    (net (code "101") (name "Net-(U2B-2IN+)") (class "Default")
      (node (ref "C16") (pin "1") (pinfunction "1_1") (pintype "passive"))
      (node (ref "R36") (pin "2") (pinfunction "2_2") (pintype "passive"))
      (node (ref "R42") (pin "2") (pinfunction "2_2") (pintype "passive"))
      (node (ref "R45") (pin "2") (pinfunction "2_2") (pintype "passive"))
      (node (ref "U2") (pin "5") (pinfunction "2IN+_5") (pintype "passive"))
    )
    (net (code "102") (name "Net-(U2B-2OUT)") (class "Default")
      (node (ref "R28") (pin "1") (pinfunction "1_1") (pintype "passive"))
      (node (ref "R34") (pin "1") (pinfunction "1_1") (pintype "passive"))
      (node (ref "R42") (pin "1") (pinfunction "1_1") (pintype "passive"))
      (node (ref "U2") (pin "2") (pinfunction "2OUT_2") (pintype "passive"))
    )
    (net (code "103") (name "Net-(U2C-3IN+)") (class "Default")
      (node (ref "C17") (pin "1") (pinfunction "1_1") (pintype "passive"))
      (node (ref "R40") (pin "2") (pinfunction "2_2") (pintype "passive"))
      (node (ref "R43") (pin "2") (pinfunction "2_2") (pintype "passive"))
      (node (ref "R47") (pin "2") (pinfunction "2_2") (pintype "passive"))
      (node (ref "U2") (pin "9") (pinfunction "3IN+_9") (pintype "passive"))
    )
    (net (code "104") (name "Net-(U2C-3OUT)") (class "Default")
      (node (ref "R31") (pin "1") (pinfunction "1_1") (pintype "passive"))
      (node (ref "R37") (pin "1") (pinfunction "1_1") (pintype "passive"))
      (node (ref "R43") (pin "1") (pinfunction "1_1") (pintype "passive"))
      (node (ref "U2") (pin "14") (pinfunction "3OUT_14") (pintype "passive"))
    )
    (net (code "105") (name "Net-(U2D-4IN+)") (class "Default")
      (node (ref "C18") (pin "1") (pinfunction "1_1") (pintype "passive"))
      (node (ref "R41") (pin "2") (pinfunction "2_2") (pintype "passive"))
      (node (ref "R44") (pin "2") (pinfunction "2_2") (pintype "passive"))
      (node (ref "R48") (pin "2") (pinfunction "2_2") (pintype "passive"))
      (node (ref "U2") (pin "11") (pinfunction "4IN+_11") (pintype "passive"))
    )
    (net (code "106") (name "Net-(U2D-4OUT)") (class "Default")
      (node (ref "R32") (pin "1") (pinfunction "1_1") (pintype "passive"))
      (node (ref "R38") (pin "1") (pinfunction "1_1") (pintype "passive"))
      (node (ref "R44") (pin "1") (pinfunction "1_1") (pintype "passive"))
      (node (ref "U2") (pin "13") (pinfunction "4OUT_13") (pintype "passive"))
    )
    (net (code "107") (name "Net-(U3A-1IN+)") (class "Default")
      (node (ref "C26") (pin "1") (pinfunction "1_1") (pintype "passive"))
      (node (ref "R57") (pin "2") (pinfunction "2_2") (pintype "passive"))
      (node (ref "R60") (pin "1") (pinfunction "1_1") (pintype "passive"))
      (node (ref "R61") (pin "2") (pinfunction "2_2") (pintype "passive"))
      (node (ref "U3") (pin "7") (pinfunction "1IN+_7") (pintype "passive"))
    )
    (net (code "108") (name "Net-(U3A-1OUT)") (class "Default")
      (node (ref "R53") (pin "1") (pinfunction "1_1") (pintype "passive"))
      (node (ref "R55") (pin "1") (pinfunction "1_1") (pintype "passive"))
      (node (ref "R60") (pin "2") (pinfunction "2_2") (pintype "passive"))
      (node (ref "U3") (pin "1") (pinfunction "1OUT_1") (pintype "passive"))
    )
    (net (code "109") (name "Net-(U3B-2IN+)") (class "Default")
      (node (ref "C27") (pin "1") (pinfunction "1_1") (pintype "passive"))
      (node (ref "R58") (pin "1") (pinfunction "1_1") (pintype "passive"))
      (node (ref "R59") (pin "2") (pinfunction "2_2") (pintype "passive"))
      (node (ref "U3") (pin "5") (pinfunction "2IN+_5") (pintype "passive"))
    )
    (net (code "110") (name "Net-(U3B-2IN-)") (class "Default")
      (node (ref "C22") (pin "2") (pinfunction "2_2") (pintype "passive"))
      (node (ref "D1") (pin "3") (pinfunction "3_3") (pintype "passive"))
      (node (ref "D2") (pin "3") (pinfunction "3_3") (pintype "passive"))
      (node (ref "D3") (pin "1") (pinfunction "1_1") (pintype "passive"))
      (node (ref "D4") (pin "3") (pinfunction "3_3") (pintype "passive"))
      (node (ref "D5") (pin "3") (pinfunction "3_3") (pintype "passive"))
      (node (ref "R52") (pin "2") (pinfunction "2_2") (pintype "passive"))
      (node (ref "U3") (pin "4") (pinfunction "2IN-_4") (pintype "passive"))
    )
    (net (code "111") (name "Net-(U3B-2OUT)") (class "Default")
      (node (ref "R54") (pin "1") (pinfunction "1_1") (pintype "passive"))
      (node (ref "R56") (pin "1") (pinfunction "1_1") (pintype "passive"))
      (node (ref "U3") (pin "2") (pinfunction "2OUT_2") (pintype "passive"))
    )
    (net (code "112") (name "Net-(U4-IN_A1)") (class "Default")
      (node (ref "R62") (pin "1") (pinfunction "1_1") (pintype "passive"))
      (node (ref "R65") (pin "2") (pinfunction "2_2") (pintype "passive"))
      (node (ref "U4") (pin "1") (pinfunction "IN_A1_1") (pintype "passive"))
      (node (ref "U4") (pin "4") (pinfunction "OUT_Y2_4") (pintype "passive"))
    )
    (net (code "113") (name "Net-(U4-IN_A2)") (class "Default")
      (node (ref "C45") (pin "1") (pinfunction "1_1") (pintype "passive"))
      (node (ref "R65") (pin "1") (pinfunction "1_1") (pintype "passive"))
      (node (ref "U4") (pin "3") (pinfunction "IN_A2_3") (pintype "passive"))
      (node (ref "Y1") (pin "3") (pinfunction "XO_3") (pintype "passive"))
    )
    (net (code "114") (name "Net-(U4-OUT_Y1)") (class "Default")
      (node (ref "R63") (pin "2") (pinfunction "2_2") (pintype "passive"))
      (node (ref "U4") (pin "6") (pinfunction "OUT_Y1_6") (pintype "passive"))
    )
    (net (code "115") (name "Net-(U4-VCC)") (class "Default")
      (node (ref "R64") (pin "2") (pinfunction "2_2") (pintype "passive"))
      (node (ref "U4") (pin "5") (pinfunction "VCC_5") (pintype "passive"))
    )
    (net (code "116") (name "Net-(U5-IN+)") (class "Default")
      (node (ref "R67") (pin "2") (pinfunction "2_2") (pintype "passive"))
      (node (ref "U5") (pin "3") (pinfunction "IN+_3") (pintype "passive"))
    )
    (net (code "117") (name "Net-(U5-IN-)") (class "Default")
      (node (ref "R66") (pin "2") (pinfunction "2_2") (pintype "passive"))
      (node (ref "U5") (pin "4") (pinfunction "IN-_4") (pintype "passive"))
    )
    (net (code "118") (name "Net-(U5-OUT+)") (class "Default")
      (node (ref "L3") (pin "2") (pinfunction "2_2") (pintype "passive"))
      (node (ref "U5") (pin "7") (pinfunction "OUT+_7") (pintype "passive"))
    )
    (net (code "119") (name "Net-(U5-OUT-)") (class "Default")
      (node (ref "L4") (pin "2") (pinfunction "2_2") (pintype "passive"))
      (node (ref "U5") (pin "6") (pinfunction "OUT-_6") (pintype "passive"))
    )
    (net (code "120") (name "Net-(U7-LPO)") (class "Default")
      (node (ref "R79") (pin "1") (pinfunction "1_1") (pintype "passive"))
      (node (ref "U7") (pin "24") (pinfunction "LPO_24") (pintype "passive"))
    )
    (net (code "121") (name "Net-(U7-SDIO_DATA_CLK)") (class "Default")
      (node (ref "R84") (pin "1") (pinfunction "1_1") (pintype "passive"))
      (node (ref "U7") (pin "17") (pinfunction "SDIO_DATA_CLK_17") (pintype "passive"))
    )
    (net (code "122") (name "Net-(U7-VIN_LDO)") (class "Default")
      (node (ref "C56") (pin "2") (pinfunction "2_2") (pintype "passive"))
      (node (ref "L2") (pin "2") (pinfunction "2_2") (pintype "passive"))
      (node (ref "U7") (pin "23") (pinfunction "VIN_LDO_23") (pintype "passive"))
    )
    (net (code "123") (name "Net-(U7-VIN_LDO_OUT)") (class "Default")
      (node (ref "L2") (pin "1") (pinfunction "1_1") (pintype "passive"))
      (node (ref "U7") (pin "21") (pinfunction "VIN_LDO_OUT_21") (pintype "passive"))
    )
    (net (code "124") (name "Net-(U7-WL_BT_ANT)") (class "Default")
      (node (ref "C48") (pin "2") (pinfunction "2_2") (pintype "passive"))
      (node (ref "C49") (pin "1") (pinfunction "1_1") (pintype "passive"))
      (node (ref "U7") (pin "2") (pinfunction "WL_BT_ANT_2") (pintype "passive"))
    )
    (net (code "125") (name "Net-(U7-WL_VDD_TCXO)") (class "Default")
      (node (ref "R75") (pin "1") (pinfunction "1_1") (pintype "passive"))
      (node (ref "U7") (pin "29") (pinfunction "WL_VDD_TCXO_29") (pintype "passive"))
    )
    (net (code "126") (name "Net-(U10-EN)") (class "Default")
      (node (ref "R101") (pin "2") (pinfunction "2_2") (pintype "passive"))
      (node (ref "R102") (pin "2") (pinfunction "2_2") (pintype "passive"))
      (node (ref "U10") (pin "4") (pinfunction "EN_4") (pintype "passive"))
    )
    (net (code "127") (name "Net-(U10-FB)") (class "Default")
      (node (ref "R103") (pin "1") (pinfunction "1_1") (pintype "passive"))
      (node (ref "R104") (pin "2") (pinfunction "2_2") (pintype "passive"))
      (node (ref "U10") (pin "3") (pinfunction "FB_3") (pintype "passive"))
    )
    (net (code "128") (name "Net-(U10-LX)") (class "Default")
      (node (ref "L1") (pin "2") (pinfunction "2_2") (pintype "passive"))
      (node (ref "U10") (pin "1") (pinfunction "LX_1") (pintype "passive"))
    )
    (net (code "129") (name "Net-(Y1-XI)") (class "Default")
      (node (ref "C34") (pin "1") (pinfunction "1_1") (pintype "passive"))
      (node (ref "R62") (pin "2") (pinfunction "2_2") (pintype "passive"))
      (node (ref "Y1") (pin "1") (pinfunction "XI_1") (pintype "passive"))
    )
    (net (code "130") (name "PS") (class "Default")
      (node (ref "C102") (pin "1") (pinfunction "1_1") (pintype "passive"))
      (node (ref "C103") (pin "2") (pinfunction "2_2") (pintype "passive"))
      (node (ref "D6") (pin "A") (pintype "passive"))
      (node (ref "L1") (pin "1") (pinfunction "1_1") (pintype "passive"))
      (node (ref "M1") (pin "10") (pinfunction "PS_10") (pintype "passive"))
      (node (ref "M1") (pin "11") (pinfunction "PS_11") (pintype "passive"))
      (node (ref "U10") (pin "6") (pinfunction "IN_6") (pintype "passive"))
    )
    (net (code "131") (name "USBVBUS") (class "Default")
      (node (ref "C42") (pin "1") (pinfunction "1_1") (pintype "passive"))
      (node (ref "C43") (pin "1") (pinfunction "1_1") (pintype "passive"))
      (node (ref "C44") (pin "2") (pinfunction "2_2") (pintype "passive"))
      (node (ref "J10") (pin "1") (pinfunction "VCC_1") (pintype "passive"))
      (node (ref "M1") (pin "12") (pinfunction "USBVBUS_12") (pintype "passive"))
    )
    (net (code "132") (name "VBAT") (class "Default")
      (node (ref "C41") (pin "1") (pinfunction "1_1") (pintype "passive"))
      (node (ref "J8") (pin "1") (pinfunction "1_1") (pintype "passive"))
      (node (ref "M1") (pin "19") (pinfunction "VBAT_19") (pintype "passive"))
      (node (ref "M1") (pin "20") (pinfunction "VBAT_20") (pintype "passive"))
    )
    (net (code "133") (name "VCC-3V0") (class "Default")
      (node (ref "C110") (pin "1") (pinfunction "1_1") (pintype "passive"))
      (node (ref "C32") (pin "2") (pinfunction "2_2") (pintype "passive"))
      (node (ref "C33") (pin "2") (pinfunction "2_2") (pintype "passive"))
      (node (ref "C37") (pin "2") (pinfunction "2_2") (pintype "passive"))
      (node (ref "J9") (pin "5") (pinfunction "VDD_5") (pintype "passive"))
      (node (ref "M1") (pin "1") (pinfunction "VCC-3V0_1") (pintype "passive"))
      (node (ref "R101") (pin "1") (pinfunction "1_1") (pintype "passive"))
      (node (ref "R68") (pin "1") (pinfunction "1_1") (pintype "passive"))
      (node (ref "R71") (pin "2") (pinfunction "2_2") (pintype "passive"))
      (node (ref "R92") (pin "2") (pinfunction "2_2") (pintype "passive"))
      (node (ref "U5") (pin "1") (pinfunction "SD_1") (pintype "passive"))
      (node (ref "U5") (pin "2") (pinfunction "ABD_2") (pintype "passive"))
      (node (ref "U5") (pin "5") (pinfunction "VDD_5") (pintype "passive"))
    )
    (net (code "134") (name "VCC-LCD") (class "Default")
      (node (ref "C10") (pin "1") (pinfunction "1_1") (pintype "passive"))
      (node (ref "C19") (pin "2") (pinfunction "2_2") (pintype "passive"))
      (node (ref "C20") (pin "1") (pinfunction "1_1") (pintype "passive"))
      (node (ref "C30") (pin "2") (pinfunction "2_2") (pintype "passive"))
      (node (ref "C31") (pin "1") (pinfunction "1_1") (pintype "passive"))
      (node (ref "C9") (pin "2") (pinfunction "2_2") (pintype "passive"))
      (node (ref "M1") (pin "4") (pinfunction "VCC-LCD_4") (pintype "passive"))
      (node (ref "R1") (pin "2") (pinfunction "2_2") (pintype "passive"))
      (node (ref "R11") (pin "1") (pinfunction "1_1") (pintype "passive"))
      (node (ref "R12") (pin "1") (pinfunction "1_1") (pintype "passive"))
      (node (ref "R15") (pin "1") (pinfunction "1_1") (pintype "passive"))
      (node (ref "R16") (pin "1") (pinfunction "1_1") (pintype "passive"))
      (node (ref "R2") (pin "2") (pinfunction "2_2") (pintype "passive"))
      (node (ref "R25") (pin "2") (pinfunction "2_2") (pintype "passive"))
      (node (ref "R26") (pin "2") (pinfunction "2_2") (pintype "passive"))
      (node (ref "R27") (pin "2") (pinfunction "2_2") (pintype "passive"))
      (node (ref "R28") (pin "2") (pinfunction "2_2") (pintype "passive"))
      (node (ref "R29") (pin "2") (pinfunction "2_2") (pintype "passive"))
      (node (ref "R3") (pin "2") (pinfunction "2_2") (pintype "passive"))
      (node (ref "R30") (pin "2") (pinfunction "2_2") (pintype "passive"))
      (node (ref "R31") (pin "2") (pinfunction "2_2") (pintype "passive"))
      (node (ref "R32") (pin "2") (pinfunction "2_2") (pintype "passive"))
      (node (ref "R35") (pin "1") (pinfunction "1_1") (pintype "passive"))
      (node (ref "R36") (pin "1") (pinfunction "1_1") (pintype "passive"))
      (node (ref "R4") (pin "2") (pinfunction "2_2") (pintype "passive"))
      (node (ref "R40") (pin "1") (pinfunction "1_1") (pintype "passive"))
      (node (ref "R41") (pin "1") (pinfunction "1_1") (pintype "passive"))
      (node (ref "R5") (pin "2") (pinfunction "2_2") (pintype "passive"))
      (node (ref "R51") (pin "2") (pinfunction "2_2") (pintype "passive"))
      (node (ref "R53") (pin "2") (pinfunction "2_2") (pintype "passive"))
      (node (ref "R54") (pin "2") (pinfunction "2_2") (pintype "passive"))
      (node (ref "R57") (pin "1") (pinfunction "1_1") (pintype "passive"))
      (node (ref "R58") (pin "2") (pinfunction "2_2") (pintype "passive"))
      (node (ref "R6") (pin "2") (pinfunction "2_2") (pintype "passive"))
      (node (ref "R7") (pin "2") (pinfunction "2_2") (pintype "passive"))
      (node (ref "R8") (pin "2") (pinfunction "2_2") (pintype "passive"))
      (node (ref "RT1") (pin "2") (pinfunction "2_2") (pintype "passive"))
      (node (ref "U1") (pin "3") (pinfunction "VCC_3") (pintype "passive"))
      (node (ref "U2") (pin "3") (pinfunction "VCC_3") (pintype "passive"))
      (node (ref "U3") (pin "3") (pinfunction "VCC_3") (pintype "passive"))
    )
    (net (code "135") (name "VCC-WIFI") (class "Default")
      (node (ref "C51") (pin "1") (pinfunction "1_1") (pintype "passive"))
      (node (ref "C55") (pin "2") (pinfunction "2_2") (pintype "passive"))
      (node (ref "C57") (pin "1") (pinfunction "1_1") (pintype "passive"))
      (node (ref "M1") (pin "3") (pinfunction "VCC-IO-WIFI_3") (pintype "passive"))
      (node (ref "R64") (pin "1") (pinfunction "1_1") (pintype "passive"))
      (node (ref "R72") (pin "1") (pinfunction "1_1") (pintype "passive"))
      (node (ref "R73") (pin "1") (pinfunction "1_1") (pintype "passive"))
      (node (ref "R75") (pin "2") (pinfunction "2_2") (pintype "passive"))
      (node (ref "R80") (pin "1") (pinfunction "1_1") (pintype "passive"))
      (node (ref "R87") (pin "1") (pinfunction "1_1") (pintype "passive"))
      (node (ref "R88") (pin "1") (pinfunction "1_1") (pintype "passive"))
      (node (ref "R89") (pin "1") (pinfunction "1_1") (pintype "passive"))
      (node (ref "R90") (pin "1") (pinfunction "1_1") (pintype "passive"))
      (node (ref "R91") (pin "1") (pinfunction "1_1") (pintype "passive"))
      (node (ref "U7") (pin "22") (pinfunction "VDDIO_22") (pintype "passive"))
      (node (ref "U7") (pin "9") (pinfunction "VBAT_9") (pintype "passive"))
    )
    (net (code "136") (name "unconnected-(M1-ACIN5V-Pad15)") (class "Default")
      (node (ref "M1") (pin "15") (pinfunction "ACIN5V_15") (pintype "passive"))
    )
    (net (code "137") (name "unconnected-(M1-ACIN5V-Pad16)") (class "Default")
      (node (ref "M1") (pin "16") (pinfunction "ACIN5V_16") (pintype "passive"))
    )
    (net (code "138") (name "unconnected-(M1-LCD-BL-EN{slash}PB7-Pad47)") (class "Default")
      (node (ref "M1") (pin "47") (pinfunction "LCD-BL-EN/PB7_47") (pintype "passive"))
    )
    (net (code "139") (name "unconnected-(M1-LCD-CLK-Pad84)") (class "Default")
      (node (ref "M1") (pin "84") (pinfunction "LCD-CLK_84") (pintype "passive"))
    )
    (net (code "140") (name "unconnected-(M1-LCD-D2-Pad102)") (class "Default")
      (node (ref "M1") (pin "102") (pinfunction "LCD-D2_102") (pintype "passive"))
    )
    (net (code "141") (name "unconnected-(M1-LCD-D3-Pad101)") (class "Default")
      (node (ref "M1") (pin "101") (pinfunction "LCD-D3_101") (pintype "passive"))
    )
    (net (code "142") (name "unconnected-(M1-LCD-D4-Pad100)") (class "Default")
      (node (ref "M1") (pin "100") (pinfunction "LCD-D4_100") (pintype "passive"))
    )
    (net (code "143") (name "unconnected-(M1-LCD-D5-Pad99)") (class "Default")
      (node (ref "M1") (pin "99") (pinfunction "LCD-D5_99") (pintype "passive"))
    )
    (net (code "144") (name "unconnected-(M1-LCD-D6-Pad98)") (class "Default")
      (node (ref "M1") (pin "98") (pinfunction "LCD-D6_98") (pintype "passive"))
    )
    (net (code "145") (name "unconnected-(M1-LCD-D20-Pad88)") (class "Default")
      (node (ref "M1") (pin "88") (pinfunction "LCD-D20_88") (pintype "passive"))
    )
    (net (code "146") (name "unconnected-(M1-LCD-D21-Pad87)") (class "Default")
      (node (ref "M1") (pin "87") (pinfunction "LCD-D21_87") (pintype "passive"))
    )
    (net (code "147") (name "unconnected-(M1-LCD-D22-Pad86)") (class "Default")
      (node (ref "M1") (pin "86") (pinfunction "LCD-D22_86") (pintype "passive"))
    )
    (net (code "148") (name "unconnected-(M1-LCD-D23-Pad85)") (class "Default")
      (node (ref "M1") (pin "85") (pinfunction "LCD-D23_85") (pintype "passive"))
    )
    (net (code "149") (name "unconnected-(M1-LCD-DE-Pad83)") (class "Default")
      (node (ref "M1") (pin "83") (pinfunction "LCD-DE_83") (pintype "passive"))
    )
    (net (code "150") (name "unconnected-(M1-LCD-HSYNC-Pad82)") (class "Default")
      (node (ref "M1") (pin "82") (pinfunction "LCD-HSYNC_82") (pintype "passive"))
    )
    (net (code "151") (name "unconnected-(M1-LCD-PWM{slash}PH0-Pad30)") (class "Default")
      (node (ref "M1") (pin "30") (pinfunction "LCD-PWM/PH0_30") (pintype "passive"))
    )
    (net (code "152") (name "unconnected-(M1-LCD-VSYNC-Pad81)") (class "Default")
      (node (ref "M1") (pin "81") (pinfunction "LCD-VSYNC_81") (pintype "passive"))
    )
    (net (code "153") (name "unconnected-(M1-NC-Pad125)") (class "Default")
      (node (ref "M1") (pin "125") (pinfunction "NC_125") (pintype "passive"))
    )
    (net (code "154") (name "unconnected-(M1-NC-Pad126)") (class "Default")
      (node (ref "M1") (pin "126") (pinfunction "NC_126") (pintype "passive"))
    )
    (net (code "155") (name "unconnected-(M1-PA-SHDN{slash}PH9-Pad39)") (class "Default")
      (node (ref "M1") (pin "39") (pinfunction "PA-SHDN/PH9_39") (pintype "passive"))
    )
    (net (code "156") (name "unconnected-(M1-PB6-Pad48)") (class "Default")
      (node (ref "M1") (pin "48") (pinfunction "PB6_48") (pintype "passive"))
    )
    (net (code "157") (name "unconnected-(M1-PE14_CSI-RST-R-Pad77)") (class "Default")
      (node (ref "M1") (pin "77") (pinfunction "PE14_CSI-RST-R_77") (pintype "passive"))
    )
    (net (code "158") (name "unconnected-(M1-PE15_CSI-STBY-R-Pad78)") (class "Default")
      (node (ref "M1") (pin "78") (pinfunction "PE15_CSI-STBY-R_78") (pintype "passive"))
    )
    (net (code "159") (name "unconnected-(M1-PL11-Pad104)") (class "Default")
      (node (ref "M1") (pin "104") (pinfunction "PL11_104") (pintype "passive"))
    )
    (net (code "160") (name "unconnected-(M1-RESET-N-Pad22)") (class "Default")
      (node (ref "M1") (pin "22") (pinfunction "RESET-N_22") (pintype "passive"))
    )
    (net (code "161") (name "unconnected-(M1-SCK1{slash}PH4-Pad49)") (class "Default")
      (node (ref "M1") (pin "49") (pinfunction "SCK1/PH4_49") (pintype "passive"))
    )
    (net (code "162") (name "unconnected-(M1-SDA1{slash}PH5-Pad50)") (class "Default")
      (node (ref "M1") (pin "50") (pinfunction "SDA1/PH5_50") (pintype "passive"))
    )
    (net (code "163") (name "unconnected-(M1-SPI0-CLK{slash}PC2-Pad61)") (class "Default")
      (node (ref "M1") (pin "61") (pinfunction "SPI0-CLK/PC2_61") (pintype "passive"))
    )
    (net (code "164") (name "unconnected-(M1-SPI0-CS{slash}PC3-Pad62)") (class "Default")
      (node (ref "M1") (pin "62") (pinfunction "SPI0-CS/PC3_62") (pintype "passive"))
    )
    (net (code "165") (name "unconnected-(M1-SPI0-MISO{slash}PC1-Pad59)") (class "Default")
      (node (ref "M1") (pin "59") (pinfunction "SPI0-MISO/PC1_59") (pintype "passive"))
    )
    (net (code "166") (name "unconnected-(M1-SPI0-MOSI{slash}PC0-Pad60)") (class "Default")
      (node (ref "M1") (pin "60") (pinfunction "SPI0-MOSI/PC0_60") (pintype "passive"))
    )
    (net (code "167") (name "unconnected-(M1-TP-RST{slash}PH1-Pad31)") (class "Default")
      (node (ref "M1") (pin "31") (pinfunction "TP-RST/PH1_31") (pintype "passive"))
    )
    (net (code "168") (name "unconnected-(M1-TP-SCK{slash}PH2-Pad32)") (class "Default")
      (node (ref "M1") (pin "32") (pinfunction "TP-SCK/PH2_32") (pintype "passive"))
    )
    (net (code "169") (name "unconnected-(M1-TP-SDA{slash}PH3-Pad33)") (class "Default")
      (node (ref "M1") (pin "33") (pinfunction "TP-SDA/PH3_33") (pintype "passive"))
    )
    (net (code "170") (name "unconnected-(M1-UART2-CTS{slash}PB3-Pad25)") (class "Default")
      (node (ref "M1") (pin "25") (pinfunction "UART2-CTS/PB3_25") (pintype "passive"))
    )
    (net (code "171") (name "unconnected-(M1-UART2-RTS{slash}PB2-Pad26)") (class "Default")
      (node (ref "M1") (pin "26") (pinfunction "UART2-RTS/PB2_26") (pintype "passive"))
    )
    (net (code "172") (name "unconnected-(M1-UART2-RX{slash}PB1-Pad23)") (class "Default")
      (node (ref "M1") (pin "23") (pinfunction "UART2-RX/PB1_23") (pintype "passive"))
    )
    (net (code "173") (name "unconnected-(M1-UART2-TX{slash}PB0-Pad24)") (class "Default")
      (node (ref "M1") (pin "24") (pinfunction "UART2-TX/PB0_24") (pintype "passive"))
    )
    (net (code "174") (name "unconnected-(M1-UART3-RX{slash}PH7-Pad27)") (class "Default")
      (node (ref "M1") (pin "27") (pinfunction "UART3-RX/PH7_27") (pintype "passive"))
    )
    (net (code "175") (name "unconnected-(M1-UART3-TX{slash}PH6-Pad28)") (class "Default")
      (node (ref "M1") (pin "28") (pinfunction "UART3-TX/PH6_28") (pintype "passive"))
    )
    (net (code "176") (name "unconnected-(M1-VBAT-EXT-Pad17)") (class "Default")
      (node (ref "M1") (pin "17") (pinfunction "VBAT-EXT_17") (pintype "passive"))
    )
    (net (code "177") (name "unconnected-(M1-VBAT-EXT-Pad18)") (class "Default")
      (node (ref "M1") (pin "18") (pinfunction "VBAT-EXT_18") (pintype "passive"))
    )
    (net (code "178") (name "unconnected-(M1-VCC-CTP-Pad6)") (class "Default")
      (node (ref "M1") (pin "6") (pinfunction "VCC-CTP_6") (pintype "passive"))
    )
    (net (code "179") (name "unconnected-(M1-VCC-RTC-Pad7)") (class "Default")
      (node (ref "M1") (pin "7") (pinfunction "VCC-RTC_7") (pintype "passive"))
    )
    (net (code "180") (name "unconnected-(U7-BT_XTAL_IN-Pad37)") (class "Default")
      (node (ref "U7") (pin "37") (pinfunction "BT_XTAL_IN_37") (pintype "passive"))
    )
    (net (code "181") (name "unconnected-(U7-BT_XTAL_OUT-Pad38)") (class "Default")
      (node (ref "U7") (pin "38") (pinfunction "BT_XTAL_OUT_38") (pintype "passive"))
    )
    (net (code "182") (name "unconnected-(U7-NC-Pad4)") (class "Default")
      (node (ref "U7") (pin "4") (pinfunction "NC_4") (pintype "passive"))
    )
    (net (code "183") (name "unconnected-(U7-NC-Pad5)") (class "Default")
      (node (ref "U7") (pin "5") (pinfunction "NC_5") (pintype "passive"))
    )
    (net (code "184") (name "unconnected-(U7-NC-Pad8)") (class "Default")
      (node (ref "U7") (pin "8") (pinfunction "NC_8") (pintype "passive"))
    )
    (net (code "185") (name "unconnected-(U7-NC-Pad10)") (class "Default")
      (node (ref "U7") (pin "10") (pinfunction "NC_10") (pintype "passive"))
    )
    (net (code "186") (name "unconnected-(U7-NC-Pad11)") (class "Default")
      (node (ref "U7") (pin "11") (pinfunction "NC_11") (pintype "passive"))
    )
    (net (code "187") (name "unconnected-(U7-NC-Pad32)") (class "Default")
      (node (ref "U7") (pin "32") (pinfunction "NC_32") (pintype "passive"))
    )
    (net (code "188") (name "unconnected-(U7-NC-Pad35)") (class "Default")
      (node (ref "U7") (pin "35") (pinfunction "NC_35") (pintype "passive"))
    )
    (net (code "189") (name "unconnected-(U7-NC-Pad39)") (class "Default")
      (node (ref "U7") (pin "39") (pinfunction "NC_39") (pintype "passive"))
    )
    (net (code "190") (name "unconnected-(U7-NC-Pad40)") (class "Default")
      (node (ref "U7") (pin "40") (pinfunction "NC_40") (pintype "passive"))
    )
    (net (code "191") (name "unconnected-(U7-NC-Pad45)") (class "Default")
      (node (ref "U7") (pin "45") (pinfunction "NC_45") (pintype "passive"))
    )
    (net (code "192") (name "unconnected-(U7-NC-Pad46)") (class "Default")
      (node (ref "U7") (pin "46") (pinfunction "NC_46") (pintype "passive"))
    )
    (net (code "193") (name "unconnected-(U7-NC-Pad47)") (class "Default")
      (node (ref "U7") (pin "47") (pinfunction "NC_47") (pintype "passive"))
    )
    (net (code "194") (name "unconnected-(U7-PCM_CLK-Pad26)") (class "Default")
      (node (ref "U7") (pin "26") (pinfunction "PCM_CLK_26") (pintype "passive"))
    )
    (net (code "195") (name "unconnected-(U7-PCM_IN-Pad27)") (class "Default")
      (node (ref "U7") (pin "27") (pinfunction "PCM_IN_27") (pintype "passive"))
    )
    (net (code "196") (name "unconnected-(U7-PCM_OUT-Pad25)") (class "Default")
      (node (ref "U7") (pin "25") (pinfunction "PCM_OUT_25") (pintype "passive"))
    )
    (net (code "197") (name "unconnected-(U7-PCM_SYNC-Pad28)") (class "Default")
      (node (ref "U7") (pin "28") (pinfunction "PCM_SYNC_28") (pintype "passive"))
    )
  )
)
